# Connector.net
KiCad netlist of a schematic drawn in Altium Designer
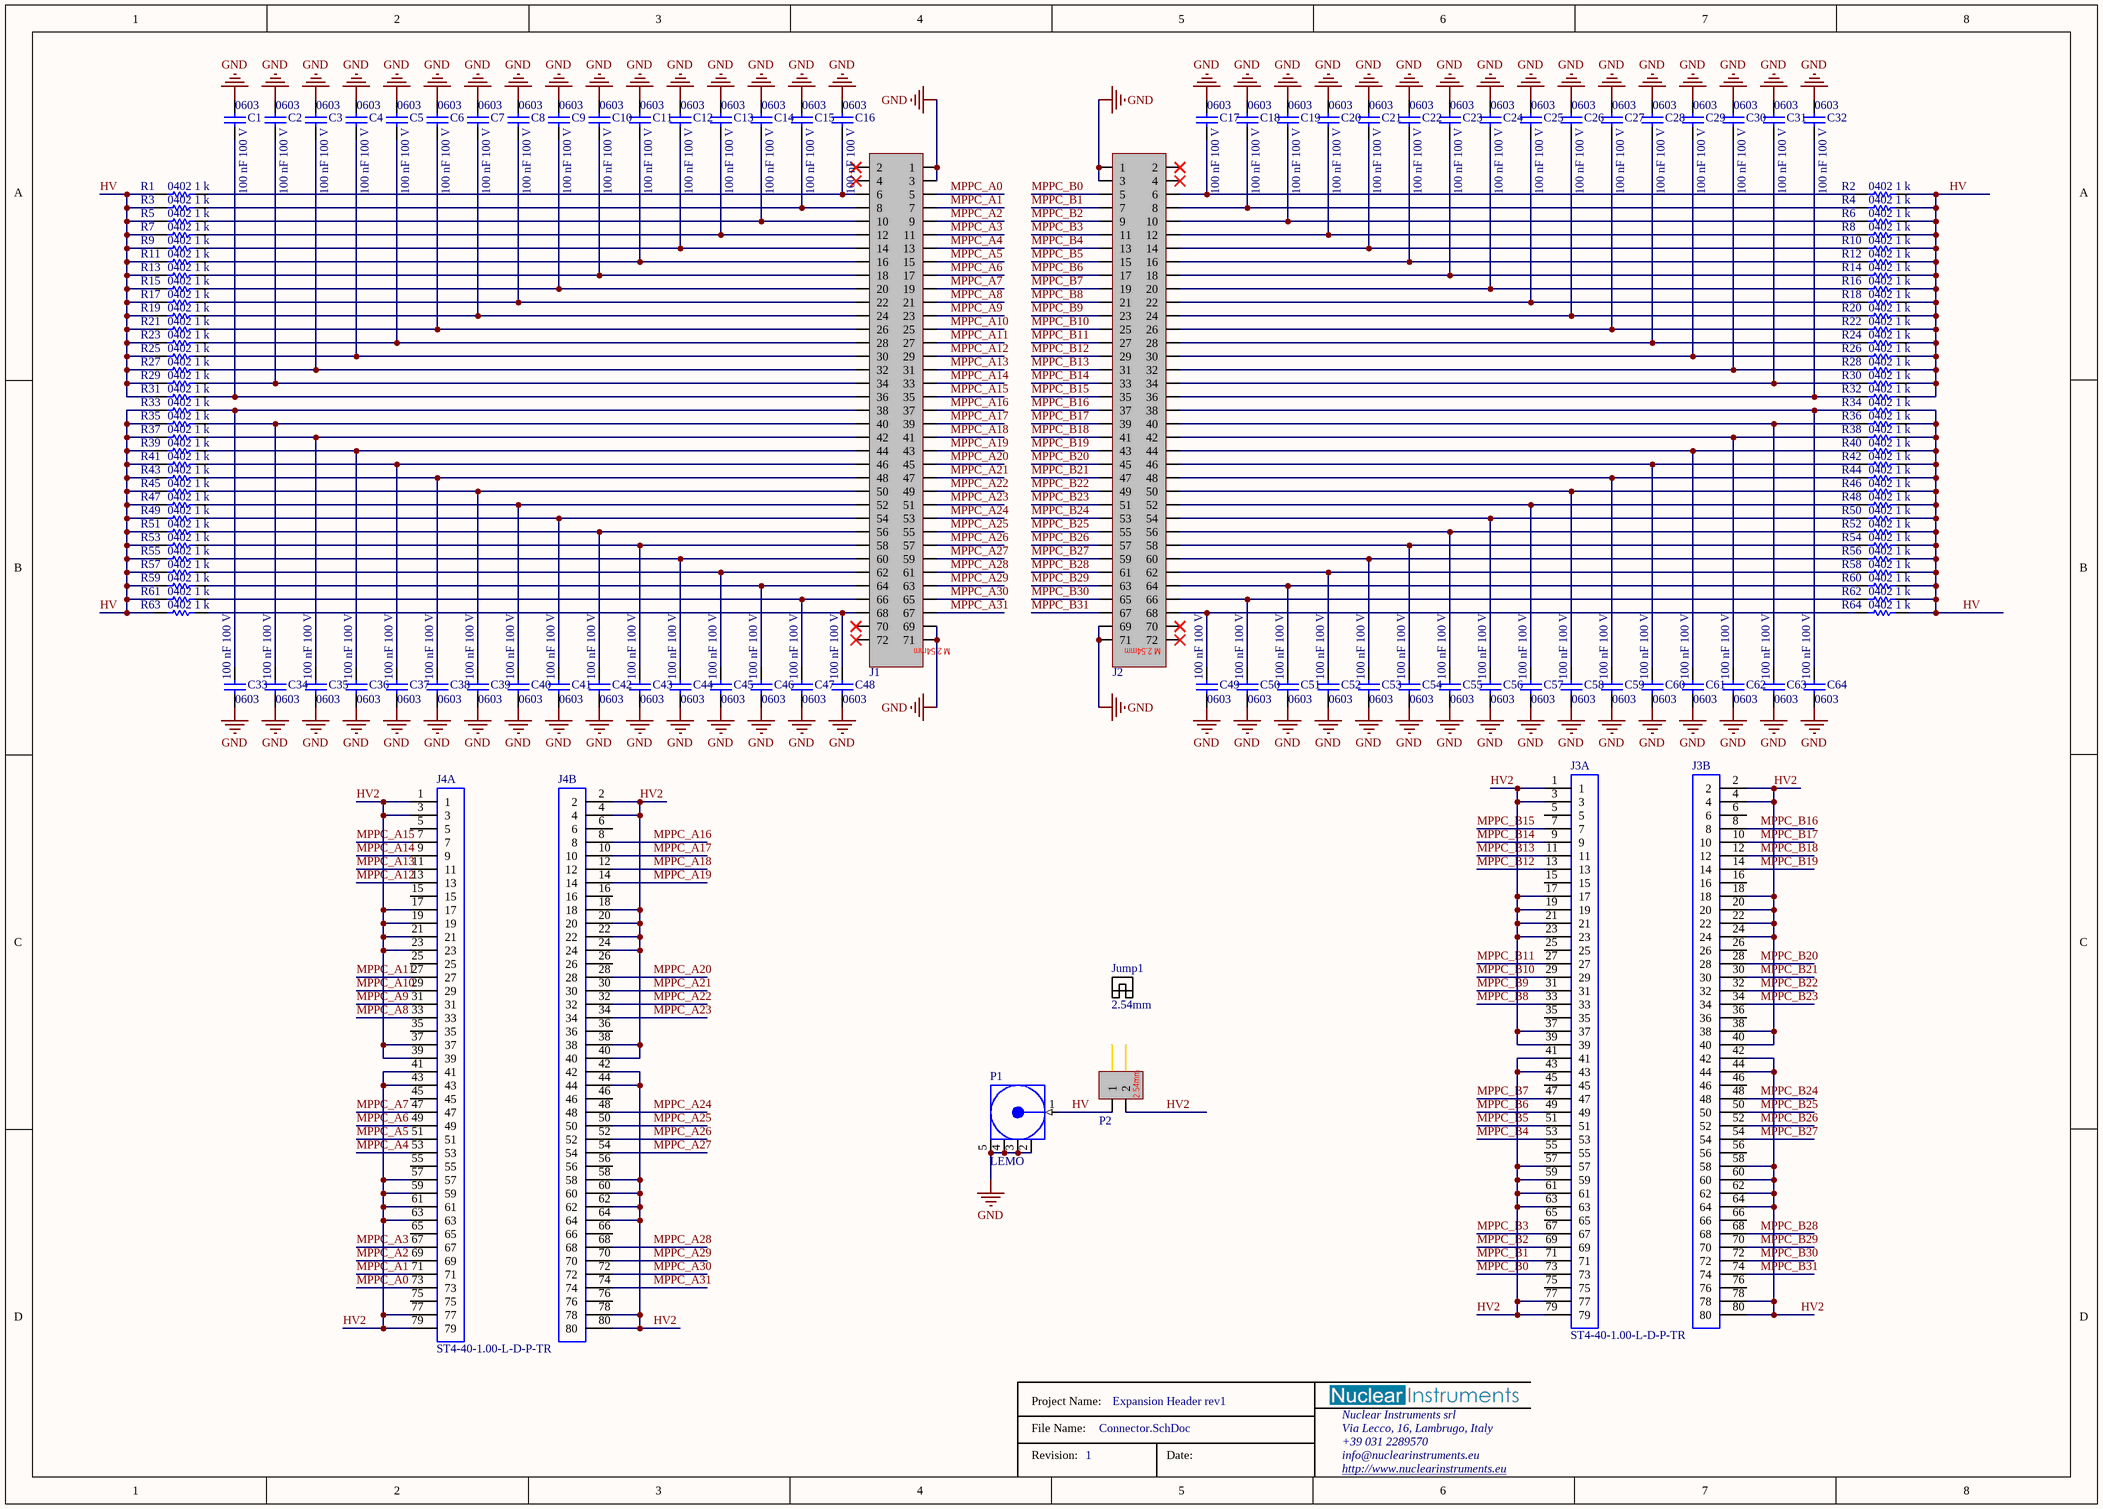
[diagram p0: Connector.SchDoc]

(export (version "E")
  (design (tool "Eeschema 10.0.6"))
  (components
    (comp (ref "C1")
      (value "0603")
      (footprint "CAPCERSMD0603")
      (fields (field (name "ALTIUM_VALUE") "100 nF 100 V"))
      (libsource (lib "0603_Cap_Cer__SARAversion-9") (part "CAPCER0603_X7R_100V_100n"))
    )
    (comp (ref "C2")
      (value "0603")
      (footprint "CAPCERSMD0603")
      (fields (field (name "ALTIUM_VALUE") "100 nF 100 V"))
      (libsource (lib "0603_Cap_Cer__SARAversion-9") (part "CAPCER0603_X7R_100V_100n"))
    )
    (comp (ref "C3")
      (value "0603")
      (footprint "CAPCERSMD0603")
      (fields (field (name "ALTIUM_VALUE") "100 nF 100 V"))
      (libsource (lib "0603_Cap_Cer__SARAversion-9") (part "CAPCER0603_X7R_100V_100n"))
    )
    (comp (ref "C4")
      (value "0603")
      (footprint "CAPCERSMD0603")
      (fields (field (name "ALTIUM_VALUE") "100 nF 100 V"))
      (libsource (lib "0603_Cap_Cer__SARAversion-9") (part "CAPCER0603_X7R_100V_100n"))
    )
    (comp (ref "C5")
      (value "0603")
      (footprint "CAPCERSMD0603")
      (fields (field (name "ALTIUM_VALUE") "100 nF 100 V"))
      (libsource (lib "0603_Cap_Cer__SARAversion-9") (part "CAPCER0603_X7R_100V_100n"))
    )
    (comp (ref "C6")
      (value "0603")
      (footprint "CAPCERSMD0603")
      (fields (field (name "ALTIUM_VALUE") "100 nF 100 V"))
      (libsource (lib "0603_Cap_Cer__SARAversion-9") (part "CAPCER0603_X7R_100V_100n"))
    )
    (comp (ref "C7")
      (value "0603")
      (footprint "CAPCERSMD0603")
      (fields (field (name "ALTIUM_VALUE") "100 nF 100 V"))
      (libsource (lib "0603_Cap_Cer__SARAversion-9") (part "CAPCER0603_X7R_100V_100n"))
    )
    (comp (ref "C8")
      (value "0603")
      (footprint "CAPCERSMD0603")
      (fields (field (name "ALTIUM_VALUE") "100 nF 100 V"))
      (libsource (lib "0603_Cap_Cer__SARAversion-9") (part "CAPCER0603_X7R_100V_100n"))
    )
    (comp (ref "C9")
      (value "0603")
      (footprint "CAPCERSMD0603")
      (fields (field (name "ALTIUM_VALUE") "100 nF 100 V"))
      (libsource (lib "0603_Cap_Cer__SARAversion-9") (part "CAPCER0603_X7R_100V_100n"))
    )
    (comp (ref "C10")
      (value "0603")
      (footprint "CAPCERSMD0603")
      (fields (field (name "ALTIUM_VALUE") "100 nF 100 V"))
      (libsource (lib "0603_Cap_Cer__SARAversion-9") (part "CAPCER0603_X7R_100V_100n"))
    )
    (comp (ref "C11")
      (value "0603")
      (footprint "CAPCERSMD0603")
      (fields (field (name "ALTIUM_VALUE") "100 nF 100 V"))
      (libsource (lib "0603_Cap_Cer__SARAversion-9") (part "CAPCER0603_X7R_100V_100n"))
    )
    (comp (ref "C12")
      (value "0603")
      (footprint "CAPCERSMD0603")
      (fields (field (name "ALTIUM_VALUE") "100 nF 100 V"))
      (libsource (lib "0603_Cap_Cer__SARAversion-9") (part "CAPCER0603_X7R_100V_100n"))
    )
    (comp (ref "C13")
      (value "0603")
      (footprint "CAPCERSMD0603")
      (fields (field (name "ALTIUM_VALUE") "100 nF 100 V"))
      (libsource (lib "0603_Cap_Cer__SARAversion-9") (part "CAPCER0603_X7R_100V_100n"))
    )
    (comp (ref "C14")
      (value "0603")
      (footprint "CAPCERSMD0603")
      (fields (field (name "ALTIUM_VALUE") "100 nF 100 V"))
      (libsource (lib "0603_Cap_Cer__SARAversion-9") (part "CAPCER0603_X7R_100V_100n"))
    )
    (comp (ref "C15")
      (value "0603")
      (footprint "CAPCERSMD0603")
      (fields (field (name "ALTIUM_VALUE") "100 nF 100 V"))
      (libsource (lib "0603_Cap_Cer__SARAversion-9") (part "CAPCER0603_X7R_100V_100n"))
    )
    (comp (ref "C16")
      (value "0603")
      (footprint "CAPCERSMD0603")
      (fields (field (name "ALTIUM_VALUE") "100 nF 100 V"))
      (libsource (lib "0603_Cap_Cer__SARAversion-9") (part "CAPCER0603_X7R_100V_100n"))
    )
    (comp (ref "C17")
      (value "0603")
      (footprint "CAPCERSMD0603")
      (fields (field (name "ALTIUM_VALUE") "100 nF 100 V"))
      (libsource (lib "0603_Cap_Cer__SARAversion-9") (part "CAPCER0603_X7R_100V_100n"))
    )
    (comp (ref "C18")
      (value "0603")
      (footprint "CAPCERSMD0603")
      (fields (field (name "ALTIUM_VALUE") "100 nF 100 V"))
      (libsource (lib "0603_Cap_Cer__SARAversion-9") (part "CAPCER0603_X7R_100V_100n"))
    )
    (comp (ref "C19")
      (value "0603")
      (footprint "CAPCERSMD0603")
      (fields (field (name "ALTIUM_VALUE") "100 nF 100 V"))
      (libsource (lib "0603_Cap_Cer__SARAversion-9") (part "CAPCER0603_X7R_100V_100n"))
    )
    (comp (ref "C20")
      (value "0603")
      (footprint "CAPCERSMD0603")
      (fields (field (name "ALTIUM_VALUE") "100 nF 100 V"))
      (libsource (lib "0603_Cap_Cer__SARAversion-9") (part "CAPCER0603_X7R_100V_100n"))
    )
    (comp (ref "C21")
      (value "0603")
      (footprint "CAPCERSMD0603")
      (fields (field (name "ALTIUM_VALUE") "100 nF 100 V"))
      (libsource (lib "0603_Cap_Cer__SARAversion-9") (part "CAPCER0603_X7R_100V_100n"))
    )
    (comp (ref "C22")
      (value "0603")
      (footprint "CAPCERSMD0603")
      (fields (field (name "ALTIUM_VALUE") "100 nF 100 V"))
      (libsource (lib "0603_Cap_Cer__SARAversion-9") (part "CAPCER0603_X7R_100V_100n"))
    )
    (comp (ref "C23")
      (value "0603")
      (footprint "CAPCERSMD0603")
      (fields (field (name "ALTIUM_VALUE") "100 nF 100 V"))
      (libsource (lib "0603_Cap_Cer__SARAversion-9") (part "CAPCER0603_X7R_100V_100n"))
    )
    (comp (ref "C24")
      (value "0603")
      (footprint "CAPCERSMD0603")
      (fields (field (name "ALTIUM_VALUE") "100 nF 100 V"))
      (libsource (lib "0603_Cap_Cer__SARAversion-9") (part "CAPCER0603_X7R_100V_100n"))
    )
    (comp (ref "C25")
      (value "0603")
      (footprint "CAPCERSMD0603")
      (fields (field (name "ALTIUM_VALUE") "100 nF 100 V"))
      (libsource (lib "0603_Cap_Cer__SARAversion-9") (part "CAPCER0603_X7R_100V_100n"))
    )
    (comp (ref "C26")
      (value "0603")
      (footprint "CAPCERSMD0603")
      (fields (field (name "ALTIUM_VALUE") "100 nF 100 V"))
      (libsource (lib "0603_Cap_Cer__SARAversion-9") (part "CAPCER0603_X7R_100V_100n"))
    )
    (comp (ref "C27")
      (value "0603")
      (footprint "CAPCERSMD0603")
      (fields (field (name "ALTIUM_VALUE") "100 nF 100 V"))
      (libsource (lib "0603_Cap_Cer__SARAversion-9") (part "CAPCER0603_X7R_100V_100n"))
    )
    (comp (ref "C28")
      (value "0603")
      (footprint "CAPCERSMD0603")
      (fields (field (name "ALTIUM_VALUE") "100 nF 100 V"))
      (libsource (lib "0603_Cap_Cer__SARAversion-9") (part "CAPCER0603_X7R_100V_100n"))
    )
    (comp (ref "C29")
      (value "0603")
      (footprint "CAPCERSMD0603")
      (fields (field (name "ALTIUM_VALUE") "100 nF 100 V"))
      (libsource (lib "0603_Cap_Cer__SARAversion-9") (part "CAPCER0603_X7R_100V_100n"))
    )
    (comp (ref "C30")
      (value "0603")
      (footprint "CAPCERSMD0603")
      (fields (field (name "ALTIUM_VALUE") "100 nF 100 V"))
      (libsource (lib "0603_Cap_Cer__SARAversion-9") (part "CAPCER0603_X7R_100V_100n"))
    )
    (comp (ref "C31")
      (value "0603")
      (footprint "CAPCERSMD0603")
      (fields (field (name "ALTIUM_VALUE") "100 nF 100 V"))
      (libsource (lib "0603_Cap_Cer__SARAversion-9") (part "CAPCER0603_X7R_100V_100n"))
    )
    (comp (ref "C32")
      (value "0603")
      (footprint "CAPCERSMD0603")
      (fields (field (name "ALTIUM_VALUE") "100 nF 100 V"))
      (libsource (lib "0603_Cap_Cer__SARAversion-9") (part "CAPCER0603_X7R_100V_100n"))
    )
    (comp (ref "C33")
      (value "0603")
      (footprint "CAPCERSMD0603")
      (fields (field (name "ALTIUM_VALUE") "100 nF 100 V"))
      (libsource (lib "0603_Cap_Cer__SARAversion-9") (part "CAPCER0603_X7R_100V_100n"))
    )
    (comp (ref "C34")
      (value "0603")
      (footprint "CAPCERSMD0603")
      (fields (field (name "ALTIUM_VALUE") "100 nF 100 V"))
      (libsource (lib "0603_Cap_Cer__SARAversion-9") (part "CAPCER0603_X7R_100V_100n"))
    )
    (comp (ref "C35")
      (value "0603")
      (footprint "CAPCERSMD0603")
      (fields (field (name "ALTIUM_VALUE") "100 nF 100 V"))
      (libsource (lib "0603_Cap_Cer__SARAversion-9") (part "CAPCER0603_X7R_100V_100n"))
    )
    (comp (ref "C36")
      (value "0603")
      (footprint "CAPCERSMD0603")
      (fields (field (name "ALTIUM_VALUE") "100 nF 100 V"))
      (libsource (lib "0603_Cap_Cer__SARAversion-9") (part "CAPCER0603_X7R_100V_100n"))
    )
    (comp (ref "C37")
      (value "0603")
      (footprint "CAPCERSMD0603")
      (fields (field (name "ALTIUM_VALUE") "100 nF 100 V"))
      (libsource (lib "0603_Cap_Cer__SARAversion-9") (part "CAPCER0603_X7R_100V_100n"))
    )
    (comp (ref "C38")
      (value "0603")
      (footprint "CAPCERSMD0603")
      (fields (field (name "ALTIUM_VALUE") "100 nF 100 V"))
      (libsource (lib "0603_Cap_Cer__SARAversion-9") (part "CAPCER0603_X7R_100V_100n"))
    )
    (comp (ref "C39")
      (value "0603")
      (footprint "CAPCERSMD0603")
      (fields (field (name "ALTIUM_VALUE") "100 nF 100 V"))
      (libsource (lib "0603_Cap_Cer__SARAversion-9") (part "CAPCER0603_X7R_100V_100n"))
    )
    (comp (ref "C40")
      (value "0603")
      (footprint "CAPCERSMD0603")
      (fields (field (name "ALTIUM_VALUE") "100 nF 100 V"))
      (libsource (lib "0603_Cap_Cer__SARAversion-9") (part "CAPCER0603_X7R_100V_100n"))
    )
    (comp (ref "C41")
      (value "0603")
      (footprint "CAPCERSMD0603")
      (fields (field (name "ALTIUM_VALUE") "100 nF 100 V"))
      (libsource (lib "0603_Cap_Cer__SARAversion-9") (part "CAPCER0603_X7R_100V_100n"))
    )
    (comp (ref "C42")
      (value "0603")
      (footprint "CAPCERSMD0603")
      (fields (field (name "ALTIUM_VALUE") "100 nF 100 V"))
      (libsource (lib "0603_Cap_Cer__SARAversion-9") (part "CAPCER0603_X7R_100V_100n"))
    )
    (comp (ref "C43")
      (value "0603")
      (footprint "CAPCERSMD0603")
      (fields (field (name "ALTIUM_VALUE") "100 nF 100 V"))
      (libsource (lib "0603_Cap_Cer__SARAversion-9") (part "CAPCER0603_X7R_100V_100n"))
    )
    (comp (ref "C44")
      (value "0603")
      (footprint "CAPCERSMD0603")
      (fields (field (name "ALTIUM_VALUE") "100 nF 100 V"))
      (libsource (lib "0603_Cap_Cer__SARAversion-9") (part "CAPCER0603_X7R_100V_100n"))
    )
    (comp (ref "C45")
      (value "0603")
      (footprint "CAPCERSMD0603")
      (fields (field (name "ALTIUM_VALUE") "100 nF 100 V"))
      (libsource (lib "0603_Cap_Cer__SARAversion-9") (part "CAPCER0603_X7R_100V_100n"))
    )
    (comp (ref "C46")
      (value "0603")
      (footprint "CAPCERSMD0603")
      (fields (field (name "ALTIUM_VALUE") "100 nF 100 V"))
      (libsource (lib "0603_Cap_Cer__SARAversion-9") (part "CAPCER0603_X7R_100V_100n"))
    )
    (comp (ref "C47")
      (value "0603")
      (footprint "CAPCERSMD0603")
      (fields (field (name "ALTIUM_VALUE") "100 nF 100 V"))
      (libsource (lib "0603_Cap_Cer__SARAversion-9") (part "CAPCER0603_X7R_100V_100n"))
    )
    (comp (ref "C48")
      (value "0603")
      (footprint "CAPCERSMD0603")
      (fields (field (name "ALTIUM_VALUE") "100 nF 100 V"))
      (libsource (lib "0603_Cap_Cer__SARAversion-9") (part "CAPCER0603_X7R_100V_100n"))
    )
    (comp (ref "C49")
      (value "0603")
      (footprint "CAPCERSMD0603")
      (fields (field (name "ALTIUM_VALUE") "100 nF 100 V"))
      (libsource (lib "0603_Cap_Cer__SARAversion-9") (part "CAPCER0603_X7R_100V_100n"))
    )
    (comp (ref "C50")
      (value "0603")
      (footprint "CAPCERSMD0603")
      (fields (field (name "ALTIUM_VALUE") "100 nF 100 V"))
      (libsource (lib "0603_Cap_Cer__SARAversion-9") (part "CAPCER0603_X7R_100V_100n"))
    )
    (comp (ref "C51")
      (value "0603")
      (footprint "CAPCERSMD0603")
      (fields (field (name "ALTIUM_VALUE") "100 nF 100 V"))
      (libsource (lib "0603_Cap_Cer__SARAversion-9") (part "CAPCER0603_X7R_100V_100n"))
    )
    (comp (ref "C52")
      (value "0603")
      (footprint "CAPCERSMD0603")
      (fields (field (name "ALTIUM_VALUE") "100 nF 100 V"))
      (libsource (lib "0603_Cap_Cer__SARAversion-9") (part "CAPCER0603_X7R_100V_100n"))
    )
    (comp (ref "C53")
      (value "0603")
      (footprint "CAPCERSMD0603")
      (fields (field (name "ALTIUM_VALUE") "100 nF 100 V"))
      (libsource (lib "0603_Cap_Cer__SARAversion-9") (part "CAPCER0603_X7R_100V_100n"))
    )
    (comp (ref "C54")
      (value "0603")
      (footprint "CAPCERSMD0603")
      (fields (field (name "ALTIUM_VALUE") "100 nF 100 V"))
      (libsource (lib "0603_Cap_Cer__SARAversion-9") (part "CAPCER0603_X7R_100V_100n"))
    )
    (comp (ref "C55")
      (value "0603")
      (footprint "CAPCERSMD0603")
      (fields (field (name "ALTIUM_VALUE") "100 nF 100 V"))
      (libsource (lib "0603_Cap_Cer__SARAversion-9") (part "CAPCER0603_X7R_100V_100n"))
    )
    (comp (ref "C56")
      (value "0603")
      (footprint "CAPCERSMD0603")
      (fields (field (name "ALTIUM_VALUE") "100 nF 100 V"))
      (libsource (lib "0603_Cap_Cer__SARAversion-9") (part "CAPCER0603_X7R_100V_100n"))
    )
    (comp (ref "C57")
      (value "0603")
      (footprint "CAPCERSMD0603")
      (fields (field (name "ALTIUM_VALUE") "100 nF 100 V"))
      (libsource (lib "0603_Cap_Cer__SARAversion-9") (part "CAPCER0603_X7R_100V_100n"))
    )
    (comp (ref "C58")
      (value "0603")
      (footprint "CAPCERSMD0603")
      (fields (field (name "ALTIUM_VALUE") "100 nF 100 V"))
      (libsource (lib "0603_Cap_Cer__SARAversion-9") (part "CAPCER0603_X7R_100V_100n"))
    )
    (comp (ref "C59")
      (value "0603")
      (footprint "CAPCERSMD0603")
      (fields (field (name "ALTIUM_VALUE") "100 nF 100 V"))
      (libsource (lib "0603_Cap_Cer__SARAversion-9") (part "CAPCER0603_X7R_100V_100n"))
    )
    (comp (ref "C60")
      (value "0603")
      (footprint "CAPCERSMD0603")
      (fields (field (name "ALTIUM_VALUE") "100 nF 100 V"))
      (libsource (lib "0603_Cap_Cer__SARAversion-9") (part "CAPCER0603_X7R_100V_100n"))
    )
    (comp (ref "C61")
      (value "0603")
      (footprint "CAPCERSMD0603")
      (fields (field (name "ALTIUM_VALUE") "100 nF 100 V"))
      (libsource (lib "0603_Cap_Cer__SARAversion-9") (part "CAPCER0603_X7R_100V_100n"))
    )
    (comp (ref "C62")
      (value "0603")
      (footprint "CAPCERSMD0603")
      (fields (field (name "ALTIUM_VALUE") "100 nF 100 V"))
      (libsource (lib "0603_Cap_Cer__SARAversion-9") (part "CAPCER0603_X7R_100V_100n"))
    )
    (comp (ref "C63")
      (value "0603")
      (footprint "CAPCERSMD0603")
      (fields (field (name "ALTIUM_VALUE") "100 nF 100 V"))
      (libsource (lib "0603_Cap_Cer__SARAversion-9") (part "CAPCER0603_X7R_100V_100n"))
    )
    (comp (ref "C64")
      (value "0603")
      (footprint "CAPCERSMD0603")
      (fields (field (name "ALTIUM_VALUE") "100 nF 100 V"))
      (libsource (lib "0603_Cap_Cer__SARAversion-9") (part "CAPCER0603_X7R_100V_100n"))
    )
    (comp (ref "J1")
      (value "Male 72 pin, dual row, 2.54 mm pitch")
      (footprint "Wurth_WR-PHD_male_2rows_vertical_2.54pitch_72ways")
      (description "WR-PHD 2.54 mm Dual Pin Header, 72p")
      (libsource (lib "Strip_Connectors__SARAversion-13") (part "Wurth_WR-PHD_male_2rows_vertical_2.54pitch_72ways"))
    )
    (comp (ref "J2")
      (value "Male 72 pin, dual row, 2.54 mm pitch")
      (footprint "Wurth_WR-PHD_male_2rows_vertical_2.54pitch_72ways")
      (description "WR-PHD 2.54 mm Dual Pin Header, 72p")
      (libsource (lib "") (part "Wurth_WR-PHD_male_2rows_vertical_2.54pitch_72ways_1"))
    )
    (comp (ref "J3")
      (value "ST4-40-1.00-L-D-P-TR")
      (footprint "Samtec_ST4-40-1.00-L-D-P-TR")
      (description "ULTRA FINE PITCH SOCKET")
      (libsource (lib "Board_Board_Connectors__SARAversion-51") (part "Samtec_ST4-40-1.00-L-D-P-TR"))
    )
    (comp (ref "J4")
      (value "ST4-40-1.00-L-D-P-TR")
      (footprint "Samtec_ST4-40-1.00-L-D-P-TR")
      (description "ULTRA FINE PITCH SOCKET")
      (libsource (lib "Board_Board_Connectors__SARAversion-51") (part "Samtec_ST4-40-1.00-L-D-P-TR"))
    )
    (comp (ref "Jump1") (value "2.54mm") (libsource (lib "Mechanical__SARAversion-68") (part "SNT-100-BK-G")))
    (comp (ref "P1")
      (value "LEMO")
      (footprint "LEMO_EPA.00.250.DTN_Vertical")
      (description "LEMO EPA 00 Vertical")
      (libsource (lib "Coaxial_Connectors__SARAversion-10") (part "LEMO_EPA.00.250.DTN_Vertical"))
    )
    (comp (ref "P2")
      (value "Wurth_WR-PHD_2way_2.54mm_male")
      (footprint "Wurth_WR-PHD_2way_2.54mm_male")
      (description "Male 2 way 2.54 mm")
      (libsource (lib "Strip_Connectors__SARAversion-13") (part "Wurth_WR-PHD_2way_2.54mm_male"))
    )
    (comp (ref "R1")
      (value "0402")
      (footprint "RESSMD0402")
      (fields (field (name "ALTIUM_VALUE") "1 k"))
      (libsource (lib "0402_Resistors__SARAversion-44") (part "RES0402-1k"))
    )
    (comp (ref "R2")
      (value "0402")
      (footprint "RESSMD0402")
      (fields (field (name "ALTIUM_VALUE") "1 k"))
      (libsource (lib "0402_Resistors__SARAversion-44") (part "RES0402-1k"))
    )
    (comp (ref "R3")
      (value "0402")
      (footprint "RESSMD0402")
      (fields (field (name "ALTIUM_VALUE") "1 k"))
      (libsource (lib "0402_Resistors__SARAversion-44") (part "RES0402-1k"))
    )
    (comp (ref "R4")
      (value "0402")
      (footprint "RESSMD0402")
      (fields (field (name "ALTIUM_VALUE") "1 k"))
      (libsource (lib "0402_Resistors__SARAversion-44") (part "RES0402-1k"))
    )
    (comp (ref "R5")
      (value "0402")
      (footprint "RESSMD0402")
      (fields (field (name "ALTIUM_VALUE") "1 k"))
      (libsource (lib "0402_Resistors__SARAversion-44") (part "RES0402-1k"))
    )
    (comp (ref "R6")
      (value "0402")
      (footprint "RESSMD0402")
      (fields (field (name "ALTIUM_VALUE") "1 k"))
      (libsource (lib "0402_Resistors__SARAversion-44") (part "RES0402-1k"))
    )
    (comp (ref "R7")
      (value "0402")
      (footprint "RESSMD0402")
      (fields (field (name "ALTIUM_VALUE") "1 k"))
      (libsource (lib "0402_Resistors__SARAversion-44") (part "RES0402-1k"))
    )
    (comp (ref "R8")
      (value "0402")
      (footprint "RESSMD0402")
      (fields (field (name "ALTIUM_VALUE") "1 k"))
      (libsource (lib "0402_Resistors__SARAversion-44") (part "RES0402-1k"))
    )
    (comp (ref "R9")
      (value "0402")
      (footprint "RESSMD0402")
      (fields (field (name "ALTIUM_VALUE") "1 k"))
      (libsource (lib "0402_Resistors__SARAversion-44") (part "RES0402-1k"))
    )
    (comp (ref "R10")
      (value "0402")
      (footprint "RESSMD0402")
      (fields (field (name "ALTIUM_VALUE") "1 k"))
      (libsource (lib "0402_Resistors__SARAversion-44") (part "RES0402-1k"))
    )
    (comp (ref "R11")
      (value "0402")
      (footprint "RESSMD0402")
      (fields (field (name "ALTIUM_VALUE") "1 k"))
      (libsource (lib "0402_Resistors__SARAversion-44") (part "RES0402-1k"))
    )
    (comp (ref "R12")
      (value "0402")
      (footprint "RESSMD0402")
      (fields (field (name "ALTIUM_VALUE") "1 k"))
      (libsource (lib "0402_Resistors__SARAversion-44") (part "RES0402-1k"))
    )
    (comp (ref "R13")
      (value "0402")
      (footprint "RESSMD0402")
      (fields (field (name "ALTIUM_VALUE") "1 k"))
      (libsource (lib "0402_Resistors__SARAversion-44") (part "RES0402-1k"))
    )
    (comp (ref "R14")
      (value "0402")
      (footprint "RESSMD0402")
      (fields (field (name "ALTIUM_VALUE") "1 k"))
      (libsource (lib "0402_Resistors__SARAversion-44") (part "RES0402-1k"))
    )
    (comp (ref "R15")
      (value "0402")
      (footprint "RESSMD0402")
      (fields (field (name "ALTIUM_VALUE") "1 k"))
      (libsource (lib "0402_Resistors__SARAversion-44") (part "RES0402-1k"))
    )
    (comp (ref "R16")
      (value "0402")
      (footprint "RESSMD0402")
      (fields (field (name "ALTIUM_VALUE") "1 k"))
      (libsource (lib "0402_Resistors__SARAversion-44") (part "RES0402-1k"))
    )
    (comp (ref "R17")
      (value "0402")
      (footprint "RESSMD0402")
      (fields (field (name "ALTIUM_VALUE") "1 k"))
      (libsource (lib "0402_Resistors__SARAversion-44") (part "RES0402-1k"))
    )
    (comp (ref "R18")
      (value "0402")
      (footprint "RESSMD0402")
      (fields (field (name "ALTIUM_VALUE") "1 k"))
      (libsource (lib "0402_Resistors__SARAversion-44") (part "RES0402-1k"))
    )
    (comp (ref "R19")
      (value "0402")
      (footprint "RESSMD0402")
      (fields (field (name "ALTIUM_VALUE") "1 k"))
      (libsource (lib "0402_Resistors__SARAversion-44") (part "RES0402-1k"))
    )
    (comp (ref "R20")
      (value "0402")
      (footprint "RESSMD0402")
      (fields (field (name "ALTIUM_VALUE") "1 k"))
      (libsource (lib "0402_Resistors__SARAversion-44") (part "RES0402-1k"))
    )
    (comp (ref "R21")
      (value "0402")
      (footprint "RESSMD0402")
      (fields (field (name "ALTIUM_VALUE") "1 k"))
      (libsource (lib "0402_Resistors__SARAversion-44") (part "RES0402-1k"))
    )
    (comp (ref "R22")
      (value "0402")
      (footprint "RESSMD0402")
      (fields (field (name "ALTIUM_VALUE") "1 k"))
      (libsource (lib "0402_Resistors__SARAversion-44") (part "RES0402-1k"))
    )
    (comp (ref "R23")
      (value "0402")
      (footprint "RESSMD0402")
      (fields (field (name "ALTIUM_VALUE") "1 k"))
      (libsource (lib "0402_Resistors__SARAversion-44") (part "RES0402-1k"))
    )
    (comp (ref "R24")
      (value "0402")
      (footprint "RESSMD0402")
      (fields (field (name "ALTIUM_VALUE") "1 k"))
      (libsource (lib "0402_Resistors__SARAversion-44") (part "RES0402-1k"))
    )
    (comp (ref "R25")
      (value "0402")
      (footprint "RESSMD0402")
      (fields (field (name "ALTIUM_VALUE") "1 k"))
      (libsource (lib "0402_Resistors__SARAversion-44") (part "RES0402-1k"))
    )
    (comp (ref "R26")
      (value "0402")
      (footprint "RESSMD0402")
      (fields (field (name "ALTIUM_VALUE") "1 k"))
      (libsource (lib "0402_Resistors__SARAversion-44") (part "RES0402-1k"))
    )
    (comp (ref "R27")
      (value "0402")
      (footprint "RESSMD0402")
      (fields (field (name "ALTIUM_VALUE") "1 k"))
      (libsource (lib "0402_Resistors__SARAversion-44") (part "RES0402-1k"))
    )
    (comp (ref "R28")
      (value "0402")
      (footprint "RESSMD0402")
      (fields (field (name "ALTIUM_VALUE") "1 k"))
      (libsource (lib "0402_Resistors__SARAversion-44") (part "RES0402-1k"))
    )
    (comp (ref "R29")
      (value "0402")
      (footprint "RESSMD0402")
      (fields (field (name "ALTIUM_VALUE") "1 k"))
      (libsource (lib "0402_Resistors__SARAversion-44") (part "RES0402-1k"))
    )
    (comp (ref "R30")
      (value "0402")
      (footprint "RESSMD0402")
      (fields (field (name "ALTIUM_VALUE") "1 k"))
      (libsource (lib "0402_Resistors__SARAversion-44") (part "RES0402-1k"))
    )
    (comp (ref "R31")
      (value "0402")
      (footprint "RESSMD0402")
      (fields (field (name "ALTIUM_VALUE") "1 k"))
      (libsource (lib "0402_Resistors__SARAversion-44") (part "RES0402-1k"))
    )
    (comp (ref "R32")
      (value "0402")
      (footprint "RESSMD0402")
      (fields (field (name "ALTIUM_VALUE") "1 k"))
      (libsource (lib "0402_Resistors__SARAversion-44") (part "RES0402-1k"))
    )
    (comp (ref "R33")
      (value "0402")
      (footprint "RESSMD0402")
      (fields (field (name "ALTIUM_VALUE") "1 k"))
      (libsource (lib "0402_Resistors__SARAversion-44") (part "RES0402-1k"))
    )
    (comp (ref "R34")
      (value "0402")
      (footprint "RESSMD0402")
      (fields (field (name "ALTIUM_VALUE") "1 k"))
      (libsource (lib "0402_Resistors__SARAversion-44") (part "RES0402-1k"))
    )
    (comp (ref "R35")
      (value "0402")
      (footprint "RESSMD0402")
      (fields (field (name "ALTIUM_VALUE") "1 k"))
      (libsource (lib "0402_Resistors__SARAversion-44") (part "RES0402-1k"))
    )
    (comp (ref "R36")
      (value "0402")
      (footprint "RESSMD0402")
      (fields (field (name "ALTIUM_VALUE") "1 k"))
      (libsource (lib "0402_Resistors__SARAversion-44") (part "RES0402-1k"))
    )
    (comp (ref "R37")
      (value "0402")
      (footprint "RESSMD0402")
      (fields (field (name "ALTIUM_VALUE") "1 k"))
      (libsource (lib "0402_Resistors__SARAversion-44") (part "RES0402-1k"))
    )
    (comp (ref "R38")
      (value "0402")
      (footprint "RESSMD0402")
      (fields (field (name "ALTIUM_VALUE") "1 k"))
      (libsource (lib "0402_Resistors__SARAversion-44") (part "RES0402-1k"))
    )
    (comp (ref "R39")
      (value "0402")
      (footprint "RESSMD0402")
      (fields (field (name "ALTIUM_VALUE") "1 k"))
      (libsource (lib "0402_Resistors__SARAversion-44") (part "RES0402-1k"))
    )
    (comp (ref "R40")
      (value "0402")
      (footprint "RESSMD0402")
      (fields (field (name "ALTIUM_VALUE") "1 k"))
      (libsource (lib "0402_Resistors__SARAversion-44") (part "RES0402-1k"))
    )
    (comp (ref "R41")
      (value "0402")
      (footprint "RESSMD0402")
      (fields (field (name "ALTIUM_VALUE") "1 k"))
      (libsource (lib "0402_Resistors__SARAversion-44") (part "RES0402-1k"))
    )
    (comp (ref "R42")
      (value "0402")
      (footprint "RESSMD0402")
      (fields (field (name "ALTIUM_VALUE") "1 k"))
      (libsource (lib "0402_Resistors__SARAversion-44") (part "RES0402-1k"))
    )
    (comp (ref "R43")
      (value "0402")
      (footprint "RESSMD0402")
      (fields (field (name "ALTIUM_VALUE") "1 k"))
      (libsource (lib "0402_Resistors__SARAversion-44") (part "RES0402-1k"))
    )
    (comp (ref "R44")
      (value "0402")
      (footprint "RESSMD0402")
      (fields (field (name "ALTIUM_VALUE") "1 k"))
      (libsource (lib "0402_Resistors__SARAversion-44") (part "RES0402-1k"))
    )
    (comp (ref "R45")
      (value "0402")
      (footprint "RESSMD0402")
      (fields (field (name "ALTIUM_VALUE") "1 k"))
      (libsource (lib "0402_Resistors__SARAversion-44") (part "RES0402-1k"))
    )
    (comp (ref "R46")
      (value "0402")
      (footprint "RESSMD0402")
      (fields (field (name "ALTIUM_VALUE") "1 k"))
      (libsource (lib "0402_Resistors__SARAversion-44") (part "RES0402-1k"))
    )
    (comp (ref "R47")
      (value "0402")
      (footprint "RESSMD0402")
      (fields (field (name "ALTIUM_VALUE") "1 k"))
      (libsource (lib "0402_Resistors__SARAversion-44") (part "RES0402-1k"))
    )
    (comp (ref "R48")
      (value "0402")
      (footprint "RESSMD0402")
      (fields (field (name "ALTIUM_VALUE") "1 k"))
      (libsource (lib "0402_Resistors__SARAversion-44") (part "RES0402-1k"))
    )
    (comp (ref "R49")
      (value "0402")
      (footprint "RESSMD0402")
      (fields (field (name "ALTIUM_VALUE") "1 k"))
      (libsource (lib "0402_Resistors__SARAversion-44") (part "RES0402-1k"))
    )
    (comp (ref "R50")
      (value "0402")
      (footprint "RESSMD0402")
      (fields (field (name "ALTIUM_VALUE") "1 k"))
      (libsource (lib "0402_Resistors__SARAversion-44") (part "RES0402-1k"))
    )
    (comp (ref "R51")
      (value "0402")
      (footprint "RESSMD0402")
      (fields (field (name "ALTIUM_VALUE") "1 k"))
      (libsource (lib "0402_Resistors__SARAversion-44") (part "RES0402-1k"))
    )
    (comp (ref "R52")
      (value "0402")
      (footprint "RESSMD0402")
      (fields (field (name "ALTIUM_VALUE") "1 k"))
      (libsource (lib "0402_Resistors__SARAversion-44") (part "RES0402-1k"))
    )
    (comp (ref "R53")
      (value "0402")
      (footprint "RESSMD0402")
      (fields (field (name "ALTIUM_VALUE") "1 k"))
      (libsource (lib "0402_Resistors__SARAversion-44") (part "RES0402-1k"))
    )
    (comp (ref "R54")
      (value "0402")
      (footprint "RESSMD0402")
      (fields (field (name "ALTIUM_VALUE") "1 k"))
      (libsource (lib "0402_Resistors__SARAversion-44") (part "RES0402-1k"))
    )
    (comp (ref "R55")
      (value "0402")
      (footprint "RESSMD0402")
      (fields (field (name "ALTIUM_VALUE") "1 k"))
      (libsource (lib "0402_Resistors__SARAversion-44") (part "RES0402-1k"))
    )
    (comp (ref "R56")
      (value "0402")
      (footprint "RESSMD0402")
      (fields (field (name "ALTIUM_VALUE") "1 k"))
      (libsource (lib "0402_Resistors__SARAversion-44") (part "RES0402-1k"))
    )
    (comp (ref "R57")
      (value "0402")
      (footprint "RESSMD0402")
      (fields (field (name "ALTIUM_VALUE") "1 k"))
      (libsource (lib "0402_Resistors__SARAversion-44") (part "RES0402-1k"))
    )
    (comp (ref "R58")
      (value "0402")
      (footprint "RESSMD0402")
      (fields (field (name "ALTIUM_VALUE") "1 k"))
      (libsource (lib "0402_Resistors__SARAversion-44") (part "RES0402-1k"))
    )
    (comp (ref "R59")
      (value "0402")
      (footprint "RESSMD0402")
      (fields (field (name "ALTIUM_VALUE") "1 k"))
      (libsource (lib "0402_Resistors__SARAversion-44") (part "RES0402-1k"))
    )
    (comp (ref "R60")
      (value "0402")
      (footprint "RESSMD0402")
      (fields (field (name "ALTIUM_VALUE") "1 k"))
      (libsource (lib "0402_Resistors__SARAversion-44") (part "RES0402-1k"))
    )
    (comp (ref "R61")
      (value "0402")
      (footprint "RESSMD0402")
      (fields (field (name "ALTIUM_VALUE") "1 k"))
      (libsource (lib "0402_Resistors__SARAversion-44") (part "RES0402-1k"))
    )
    (comp (ref "R62")
      (value "0402")
      (footprint "RESSMD0402")
      (fields (field (name "ALTIUM_VALUE") "1 k"))
      (libsource (lib "0402_Resistors__SARAversion-44") (part "RES0402-1k"))
    )
    (comp (ref "R63")
      (value "0402")
      (footprint "RESSMD0402")
      (fields (field (name "ALTIUM_VALUE") "1 k"))
      (libsource (lib "0402_Resistors__SARAversion-44") (part "RES0402-1k"))
    )
    (comp (ref "R64")
      (value "0402")
      (footprint "RESSMD0402")
      (fields (field (name "ALTIUM_VALUE") "1 k"))
      (libsource (lib "0402_Resistors__SARAversion-44") (part "RES0402-1k"))
    )
  )
  (nets
    (net (code "1") (name "/HV") (class "Default")
      (node (ref "P1") (pin "1") (pinfunction "Signal_1") (pintype "input"))
      (node (ref "P2") (pin "1") (pinfunction "1_1") (pintype "passive"))
      (node (ref "R1") (pin "1") (pinfunction "1_1") (pintype "passive"))
      (node (ref "R10") (pin "2") (pinfunction "2_2") (pintype "passive"))
      (node (ref "R11") (pin "1") (pinfunction "1_1") (pintype "passive"))
      (node (ref "R12") (pin "2") (pinfunction "2_2") (pintype "passive"))
      (node (ref "R13") (pin "1") (pinfunction "1_1") (pintype "passive"))
      (node (ref "R14") (pin "2") (pinfunction "2_2") (pintype "passive"))
      (node (ref "R15") (pin "1") (pinfunction "1_1") (pintype "passive"))
      (node (ref "R16") (pin "2") (pinfunction "2_2") (pintype "passive"))
      (node (ref "R17") (pin "1") (pinfunction "1_1") (pintype "passive"))
      (node (ref "R18") (pin "2") (pinfunction "2_2") (pintype "passive"))
      (node (ref "R19") (pin "1") (pinfunction "1_1") (pintype "passive"))
      (node (ref "R2") (pin "2") (pinfunction "2_2") (pintype "passive"))
      (node (ref "R20") (pin "2") (pinfunction "2_2") (pintype "passive"))
      (node (ref "R21") (pin "1") (pinfunction "1_1") (pintype "passive"))
      (node (ref "R22") (pin "2") (pinfunction "2_2") (pintype "passive"))
      (node (ref "R23") (pin "1") (pinfunction "1_1") (pintype "passive"))
      (node (ref "R24") (pin "2") (pinfunction "2_2") (pintype "passive"))
      (node (ref "R25") (pin "1") (pinfunction "1_1") (pintype "passive"))
      (node (ref "R26") (pin "2") (pinfunction "2_2") (pintype "passive"))
      (node (ref "R27") (pin "1") (pinfunction "1_1") (pintype "passive"))
      (node (ref "R28") (pin "2") (pinfunction "2_2") (pintype "passive"))
      (node (ref "R29") (pin "1") (pinfunction "1_1") (pintype "passive"))
      (node (ref "R3") (pin "1") (pinfunction "1_1") (pintype "passive"))
      (node (ref "R30") (pin "2") (pinfunction "2_2") (pintype "passive"))
      (node (ref "R31") (pin "1") (pinfunction "1_1") (pintype "passive"))
      (node (ref "R32") (pin "2") (pinfunction "2_2") (pintype "passive"))
      (node (ref "R33") (pin "1") (pinfunction "1_1") (pintype "passive"))
      (node (ref "R34") (pin "2") (pinfunction "2_2") (pintype "passive"))
      (node (ref "R35") (pin "1") (pinfunction "1_1") (pintype "passive"))
      (node (ref "R36") (pin "2") (pinfunction "2_2") (pintype "passive"))
      (node (ref "R37") (pin "1") (pinfunction "1_1") (pintype "passive"))
      (node (ref "R38") (pin "2") (pinfunction "2_2") (pintype "passive"))
      (node (ref "R39") (pin "1") (pinfunction "1_1") (pintype "passive"))
      (node (ref "R4") (pin "2") (pinfunction "2_2") (pintype "passive"))
      (node (ref "R40") (pin "2") (pinfunction "2_2") (pintype "passive"))
      (node (ref "R41") (pin "1") (pinfunction "1_1") (pintype "passive"))
      (node (ref "R42") (pin "2") (pinfunction "2_2") (pintype "passive"))
      (node (ref "R43") (pin "1") (pinfunction "1_1") (pintype "passive"))
      (node (ref "R44") (pin "2") (pinfunction "2_2") (pintype "passive"))
      (node (ref "R45") (pin "1") (pinfunction "1_1") (pintype "passive"))
      (node (ref "R46") (pin "2") (pinfunction "2_2") (pintype "passive"))
      (node (ref "R47") (pin "1") (pinfunction "1_1") (pintype "passive"))
      (node (ref "R48") (pin "2") (pinfunction "2_2") (pintype "passive"))
      (node (ref "R49") (pin "1") (pinfunction "1_1") (pintype "passive"))
      (node (ref "R5") (pin "1") (pinfunction "1_1") (pintype "passive"))
      (node (ref "R50") (pin "2") (pinfunction "2_2") (pintype "passive"))
      (node (ref "R51") (pin "1") (pinfunction "1_1") (pintype "passive"))
      (node (ref "R52") (pin "2") (pinfunction "2_2") (pintype "passive"))
      (node (ref "R53") (pin "1") (pinfunction "1_1") (pintype "passive"))
      (node (ref "R54") (pin "2") (pinfunction "2_2") (pintype "passive"))
      (node (ref "R55") (pin "1") (pinfunction "1_1") (pintype "passive"))
      (node (ref "R56") (pin "2") (pinfunction "2_2") (pintype "passive"))
      (node (ref "R57") (pin "1") (pinfunction "1_1") (pintype "passive"))
      (node (ref "R58") (pin "2") (pinfunction "2_2") (pintype "passive"))
      (node (ref "R59") (pin "1") (pinfunction "1_1") (pintype "passive"))
      (node (ref "R6") (pin "2") (pinfunction "2_2") (pintype "passive"))
      (node (ref "R60") (pin "2") (pinfunction "2_2") (pintype "passive"))
      (node (ref "R61") (pin "1") (pinfunction "1_1") (pintype "passive"))
      (node (ref "R62") (pin "2") (pinfunction "2_2") (pintype "passive"))
      (node (ref "R63") (pin "1") (pinfunction "1_1") (pintype "passive"))
      (node (ref "R64") (pin "2") (pinfunction "2_2") (pintype "passive"))
      (node (ref "R7") (pin "1") (pinfunction "1_1") (pintype "passive"))
      (node (ref "R8") (pin "2") (pinfunction "2_2") (pintype "passive"))
      (node (ref "R9") (pin "1") (pinfunction "1_1") (pintype "passive"))
    )
    (net (code "2") (name "/HV2") (class "Default")
      (node (ref "J3") (pin "1") (pinfunction "1_1") (pintype "passive"))
      (node (ref "J3") (pin "17") (pinfunction "17_17") (pintype "passive"))
      (node (ref "J3") (pin "18") (pinfunction "18_18") (pintype "passive"))
      (node (ref "J3") (pin "19") (pinfunction "19_19") (pintype "passive"))
      (node (ref "J3") (pin "2") (pinfunction "2_2") (pintype "passive"))
      (node (ref "J3") (pin "20") (pinfunction "20_20") (pintype "passive"))
      (node (ref "J3") (pin "21") (pinfunction "21_21") (pintype "passive"))
      (node (ref "J3") (pin "22") (pinfunction "22_22") (pintype "passive"))
      (node (ref "J3") (pin "23") (pinfunction "23_23") (pintype "passive"))
      (node (ref "J3") (pin "24") (pinfunction "24_24") (pintype "passive"))
      (node (ref "J3") (pin "3") (pinfunction "3_3") (pintype "passive"))
      (node (ref "J3") (pin "37") (pinfunction "37_37") (pintype "passive"))
      (node (ref "J3") (pin "38") (pinfunction "38_38") (pintype "passive"))
      (node (ref "J3") (pin "39") (pinfunction "39_39") (pintype "passive"))
      (node (ref "J3") (pin "4") (pinfunction "4_4") (pintype "passive"))
      (node (ref "J3") (pin "40") (pinfunction "40_40") (pintype "passive"))
      (node (ref "J3") (pin "41") (pinfunction "41_41") (pintype "passive"))
      (node (ref "J3") (pin "42") (pinfunction "42_42") (pintype "passive"))
      (node (ref "J3") (pin "43") (pinfunction "43_43") (pintype "passive"))
      (node (ref "J3") (pin "44") (pinfunction "44_44") (pintype "passive"))
      (node (ref "J3") (pin "57") (pinfunction "57_57") (pintype "passive"))
      (node (ref "J3") (pin "58") (pinfunction "58_58") (pintype "passive"))
      (node (ref "J3") (pin "59") (pinfunction "59_59") (pintype "passive"))
      (node (ref "J3") (pin "60") (pinfunction "60_60") (pintype "passive"))
      (node (ref "J3") (pin "61") (pinfunction "61_61") (pintype "passive"))
      (node (ref "J3") (pin "62") (pinfunction "62_62") (pintype "passive"))
      (node (ref "J3") (pin "63") (pinfunction "63_63") (pintype "passive"))
      (node (ref "J3") (pin "64") (pinfunction "64_64") (pintype "passive"))
      (node (ref "J3") (pin "77") (pinfunction "77_77") (pintype "passive"))
      (node (ref "J3") (pin "78") (pinfunction "78_78") (pintype "passive"))
      (node (ref "J3") (pin "79") (pinfunction "79_79") (pintype "passive"))
      (node (ref "J3") (pin "80") (pinfunction "80_80") (pintype "passive"))
      (node (ref "J4") (pin "1") (pinfunction "1_1") (pintype "passive"))
      (node (ref "J4") (pin "17") (pinfunction "17_17") (pintype "passive"))
      (node (ref "J4") (pin "18") (pinfunction "18_18") (pintype "passive"))
      (node (ref "J4") (pin "19") (pinfunction "19_19") (pintype "passive"))
      (node (ref "J4") (pin "2") (pinfunction "2_2") (pintype "passive"))
      (node (ref "J4") (pin "20") (pinfunction "20_20") (pintype "passive"))
      (node (ref "J4") (pin "21") (pinfunction "21_21") (pintype "passive"))
      (node (ref "J4") (pin "22") (pinfunction "22_22") (pintype "passive"))
      (node (ref "J4") (pin "23") (pinfunction "23_23") (pintype "passive"))
      (node (ref "J4") (pin "24") (pinfunction "24_24") (pintype "passive"))
      (node (ref "J4") (pin "3") (pinfunction "3_3") (pintype "passive"))
      (node (ref "J4") (pin "37") (pinfunction "37_37") (pintype "passive"))
      (node (ref "J4") (pin "38") (pinfunction "38_38") (pintype "passive"))
      (node (ref "J4") (pin "39") (pinfunction "39_39") (pintype "passive"))
      (node (ref "J4") (pin "4") (pinfunction "4_4") (pintype "passive"))
      (node (ref "J4") (pin "40") (pinfunction "40_40") (pintype "passive"))
      (node (ref "J4") (pin "41") (pinfunction "41_41") (pintype "passive"))
      (node (ref "J4") (pin "42") (pinfunction "42_42") (pintype "passive"))
      (node (ref "J4") (pin "43") (pinfunction "43_43") (pintype "passive"))
      (node (ref "J4") (pin "44") (pinfunction "44_44") (pintype "passive"))
      (node (ref "J4") (pin "57") (pinfunction "57_57") (pintype "passive"))
      (node (ref "J4") (pin "58") (pinfunction "58_58") (pintype "passive"))
      (node (ref "J4") (pin "59") (pinfunction "59_59") (pintype "passive"))
      (node (ref "J4") (pin "60") (pinfunction "60_60") (pintype "passive"))
      (node (ref "J4") (pin "61") (pinfunction "61_61") (pintype "passive"))
      (node (ref "J4") (pin "62") (pinfunction "62_62") (pintype "passive"))
      (node (ref "J4") (pin "63") (pinfunction "63_63") (pintype "passive"))
      (node (ref "J4") (pin "64") (pinfunction "64_64") (pintype "passive"))
      (node (ref "J4") (pin "77") (pinfunction "77_77") (pintype "passive"))
      (node (ref "J4") (pin "78") (pinfunction "78_78") (pintype "passive"))
      (node (ref "J4") (pin "79") (pinfunction "79_79") (pintype "passive"))
      (node (ref "J4") (pin "80") (pinfunction "80_80") (pintype "passive"))
      (node (ref "P2") (pin "2") (pinfunction "2_2") (pintype "passive"))
    )
    (net (code "3") (name "/MPPC_A0") (class "Default")
      (node (ref "J1") (pin "5") (pinfunction "5_5") (pintype "passive"))
      (node (ref "J4") (pin "73") (pinfunction "73_73") (pintype "passive"))
    )
    (net (code "4") (name "/MPPC_A1") (class "Default")
      (node (ref "J1") (pin "7") (pinfunction "7_7") (pintype "passive"))
      (node (ref "J4") (pin "71") (pinfunction "71_71") (pintype "passive"))
    )
    (net (code "5") (name "/MPPC_A2") (class "Default")
      (node (ref "J1") (pin "9") (pinfunction "9_9") (pintype "passive"))
      (node (ref "J4") (pin "69") (pinfunction "69_69") (pintype "passive"))
    )
    (net (code "6") (name "/MPPC_A3") (class "Default")
      (node (ref "J1") (pin "11") (pinfunction "11_11") (pintype "passive"))
      (node (ref "J4") (pin "67") (pinfunction "67_67") (pintype "passive"))
    )
    (net (code "7") (name "/MPPC_A4") (class "Default")
      (node (ref "J1") (pin "13") (pinfunction "13_13") (pintype "passive"))
      (node (ref "J4") (pin "53") (pinfunction "53_53") (pintype "passive"))
    )
    (net (code "8") (name "/MPPC_A5") (class "Default")
      (node (ref "J1") (pin "15") (pinfunction "15_15") (pintype "passive"))
      (node (ref "J4") (pin "51") (pinfunction "51_51") (pintype "passive"))
    )
    (net (code "9") (name "/MPPC_A6") (class "Default")
      (node (ref "J1") (pin "17") (pinfunction "17_17") (pintype "passive"))
      (node (ref "J4") (pin "49") (pinfunction "49_49") (pintype "passive"))
    )
    (net (code "10") (name "/MPPC_A7") (class "Default")
      (node (ref "J1") (pin "19") (pinfunction "19_19") (pintype "passive"))
      (node (ref "J4") (pin "47") (pinfunction "47_47") (pintype "passive"))
    )
    (net (code "11") (name "/MPPC_A8") (class "Default")
      (node (ref "J1") (pin "21") (pinfunction "21_21") (pintype "passive"))
      (node (ref "J4") (pin "33") (pinfunction "33_33") (pintype "passive"))
    )
    (net (code "12") (name "/MPPC_A9") (class "Default")
      (node (ref "J1") (pin "23") (pinfunction "23_23") (pintype "passive"))
      (node (ref "J4") (pin "31") (pinfunction "31_31") (pintype "passive"))
    )
    (net (code "13") (name "/MPPC_A10") (class "Default")
      (node (ref "J1") (pin "25") (pinfunction "25_25") (pintype "passive"))
      (node (ref "J4") (pin "29") (pinfunction "29_29") (pintype "passive"))
    )
    (net (code "14") (name "/MPPC_A11") (class "Default")
      (node (ref "J1") (pin "27") (pinfunction "27_27") (pintype "passive"))
      (node (ref "J4") (pin "27") (pinfunction "27_27") (pintype "passive"))
    )
    (net (code "15") (name "/MPPC_A12") (class "Default")
      (node (ref "J1") (pin "29") (pinfunction "29_29") (pintype "passive"))
      (node (ref "J4") (pin "13") (pinfunction "13_13") (pintype "passive"))
    )
    (net (code "16") (name "/MPPC_A13") (class "Default")
      (node (ref "J1") (pin "31") (pinfunction "31_31") (pintype "passive"))
      (node (ref "J4") (pin "11") (pinfunction "11_11") (pintype "passive"))
    )
    (net (code "17") (name "/MPPC_A14") (class "Default")
      (node (ref "J1") (pin "33") (pinfunction "33_33") (pintype "passive"))
      (node (ref "J4") (pin "9") (pinfunction "9_9") (pintype "passive"))
    )
    (net (code "18") (name "/MPPC_A15") (class "Default")
      (node (ref "J1") (pin "35") (pinfunction "35_35") (pintype "passive"))
      (node (ref "J4") (pin "7") (pinfunction "7_7") (pintype "passive"))
    )
    (net (code "19") (name "/MPPC_A16") (class "Default")
      (node (ref "J1") (pin "37") (pinfunction "37_37") (pintype "passive"))
      (node (ref "J4") (pin "8") (pinfunction "8_8") (pintype "passive"))
    )
    (net (code "20") (name "/MPPC_A17") (class "Default")
      (node (ref "J1") (pin "39") (pinfunction "39_39") (pintype "passive"))
      (node (ref "J4") (pin "10") (pinfunction "10_10") (pintype "passive"))
    )
    (net (code "21") (name "/MPPC_A18") (class "Default")
      (node (ref "J1") (pin "41") (pinfunction "41_41") (pintype "passive"))
      (node (ref "J4") (pin "12") (pinfunction "12_12") (pintype "passive"))
    )
    (net (code "22") (name "/MPPC_A19") (class "Default")
      (node (ref "J1") (pin "43") (pinfunction "43_43") (pintype "passive"))
      (node (ref "J4") (pin "14") (pinfunction "14_14") (pintype "passive"))
    )
    (net (code "23") (name "/MPPC_A20") (class "Default")
      (node (ref "J1") (pin "45") (pinfunction "45_45") (pintype "passive"))
      (node (ref "J4") (pin "28") (pinfunction "28_28") (pintype "passive"))
    )
    (net (code "24") (name "/MPPC_A21") (class "Default")
      (node (ref "J1") (pin "47") (pinfunction "47_47") (pintype "passive"))
      (node (ref "J4") (pin "30") (pinfunction "30_30") (pintype "passive"))
    )
    (net (code "25") (name "/MPPC_A22") (class "Default")
      (node (ref "J1") (pin "49") (pinfunction "49_49") (pintype "passive"))
      (node (ref "J4") (pin "32") (pinfunction "32_32") (pintype "passive"))
    )
    (net (code "26") (name "/MPPC_A23") (class "Default")
      (node (ref "J1") (pin "51") (pinfunction "51_51") (pintype "passive"))
      (node (ref "J4") (pin "34") (pinfunction "34_34") (pintype "passive"))
    )
    (net (code "27") (name "/MPPC_A24") (class "Default")
      (node (ref "J1") (pin "53") (pinfunction "53_53") (pintype "passive"))
      (node (ref "J4") (pin "48") (pinfunction "48_48") (pintype "passive"))
    )
    (net (code "28") (name "/MPPC_A25") (class "Default")
      (node (ref "J1") (pin "55") (pinfunction "55_55") (pintype "passive"))
      (node (ref "J4") (pin "50") (pinfunction "50_50") (pintype "passive"))
    )
    (net (code "29") (name "/MPPC_A26") (class "Default")
      (node (ref "J1") (pin "57") (pinfunction "57_57") (pintype "passive"))
      (node (ref "J4") (pin "52") (pinfunction "52_52") (pintype "passive"))
    )
    (net (code "30") (name "/MPPC_A27") (class "Default")
      (node (ref "J1") (pin "59") (pinfunction "59_59") (pintype "passive"))
      (node (ref "J4") (pin "54") (pinfunction "54_54") (pintype "passive"))
    )
    (net (code "31") (name "/MPPC_A28") (class "Default")
      (node (ref "J1") (pin "61") (pinfunction "61_61") (pintype "passive"))
      (node (ref "J4") (pin "68") (pinfunction "68_68") (pintype "passive"))
    )
    (net (code "32") (name "/MPPC_A29") (class "Default")
      (node (ref "J1") (pin "63") (pinfunction "63_63") (pintype "passive"))
      (node (ref "J4") (pin "70") (pinfunction "70_70") (pintype "passive"))
    )
    (net (code "33") (name "/MPPC_A30") (class "Default")
      (node (ref "J1") (pin "65") (pinfunction "65_65") (pintype "passive"))
      (node (ref "J4") (pin "72") (pinfunction "72_72") (pintype "passive"))
    )
    (net (code "34") (name "/MPPC_A31") (class "Default")
      (node (ref "J1") (pin "67") (pinfunction "67_67") (pintype "passive"))
      (node (ref "J4") (pin "74") (pinfunction "74_74") (pintype "passive"))
    )
    (net (code "35") (name "/MPPC_B0") (class "Default")
      (node (ref "J2") (pin "5") (pinfunction "5_5") (pintype "passive"))
      (node (ref "J3") (pin "73") (pinfunction "73_73") (pintype "passive"))
    )
    (net (code "36") (name "/MPPC_B1") (class "Default")
      (node (ref "J2") (pin "7") (pinfunction "7_7") (pintype "passive"))
      (node (ref "J3") (pin "71") (pinfunction "71_71") (pintype "passive"))
    )
    (net (code "37") (name "/MPPC_B2") (class "Default")
      (node (ref "J2") (pin "9") (pinfunction "9_9") (pintype "passive"))
      (node (ref "J3") (pin "69") (pinfunction "69_69") (pintype "passive"))
    )
    (net (code "38") (name "/MPPC_B3") (class "Default")
      (node (ref "J2") (pin "11") (pinfunction "11_11") (pintype "passive"))
      (node (ref "J3") (pin "67") (pinfunction "67_67") (pintype "passive"))
    )
    (net (code "39") (name "/MPPC_B4") (class "Default")
      (node (ref "J2") (pin "13") (pinfunction "13_13") (pintype "passive"))
      (node (ref "J3") (pin "53") (pinfunction "53_53") (pintype "passive"))
    )
    (net (code "40") (name "/MPPC_B5") (class "Default")
      (node (ref "J2") (pin "15") (pinfunction "15_15") (pintype "passive"))
      (node (ref "J3") (pin "51") (pinfunction "51_51") (pintype "passive"))
    )
    (net (code "41") (name "/MPPC_B6") (class "Default")
      (node (ref "J2") (pin "17") (pinfunction "17_17") (pintype "passive"))
      (node (ref "J3") (pin "49") (pinfunction "49_49") (pintype "passive"))
    )
    (net (code "42") (name "/MPPC_B7") (class "Default")
      (node (ref "J2") (pin "19") (pinfunction "19_19") (pintype "passive"))
      (node (ref "J3") (pin "47") (pinfunction "47_47") (pintype "passive"))
    )
    (net (code "43") (name "/MPPC_B8") (class "Default")
      (node (ref "J2") (pin "21") (pinfunction "21_21") (pintype "passive"))
      (node (ref "J3") (pin "33") (pinfunction "33_33") (pintype "passive"))
    )
    (net (code "44") (name "/MPPC_B9") (class "Default")
      (node (ref "J2") (pin "23") (pinfunction "23_23") (pintype "passive"))
      (node (ref "J3") (pin "31") (pinfunction "31_31") (pintype "passive"))
    )
    (net (code "45") (name "/MPPC_B10") (class "Default")
      (node (ref "J2") (pin "25") (pinfunction "25_25") (pintype "passive"))
      (node (ref "J3") (pin "29") (pinfunction "29_29") (pintype "passive"))
    )
    (net (code "46") (name "/MPPC_B11") (class "Default")
      (node (ref "J2") (pin "27") (pinfunction "27_27") (pintype "passive"))
      (node (ref "J3") (pin "27") (pinfunction "27_27") (pintype "passive"))
    )
    (net (code "47") (name "/MPPC_B12") (class "Default")
      (node (ref "J2") (pin "29") (pinfunction "29_29") (pintype "passive"))
      (node (ref "J3") (pin "13") (pinfunction "13_13") (pintype "passive"))
    )
    (net (code "48") (name "/MPPC_B13") (class "Default")
      (node (ref "J2") (pin "31") (pinfunction "31_31") (pintype "passive"))
      (node (ref "J3") (pin "11") (pinfunction "11_11") (pintype "passive"))
    )
    (net (code "49") (name "/MPPC_B14") (class "Default")
      (node (ref "J2") (pin "33") (pinfunction "33_33") (pintype "passive"))
      (node (ref "J3") (pin "9") (pinfunction "9_9") (pintype "passive"))
    )
    (net (code "50") (name "/MPPC_B15") (class "Default")
      (node (ref "J2") (pin "35") (pinfunction "35_35") (pintype "passive"))
      (node (ref "J3") (pin "7") (pinfunction "7_7") (pintype "passive"))
    )
    (net (code "51") (name "/MPPC_B16") (class "Default")
      (node (ref "J2") (pin "37") (pinfunction "37_37") (pintype "passive"))
      (node (ref "J3") (pin "8") (pinfunction "8_8") (pintype "passive"))
    )
    (net (code "52") (name "/MPPC_B17") (class "Default")
      (node (ref "J2") (pin "39") (pinfunction "39_39") (pintype "passive"))
      (node (ref "J3") (pin "10") (pinfunction "10_10") (pintype "passive"))
    )
    (net (code "53") (name "/MPPC_B18") (class "Default")
      (node (ref "J2") (pin "41") (pinfunction "41_41") (pintype "passive"))
      (node (ref "J3") (pin "12") (pinfunction "12_12") (pintype "passive"))
    )
    (net (code "54") (name "/MPPC_B19") (class "Default")
      (node (ref "J2") (pin "43") (pinfunction "43_43") (pintype "passive"))
      (node (ref "J3") (pin "14") (pinfunction "14_14") (pintype "passive"))
    )
    (net (code "55") (name "/MPPC_B20") (class "Default")
      (node (ref "J2") (pin "45") (pinfunction "45_45") (pintype "passive"))
      (node (ref "J3") (pin "28") (pinfunction "28_28") (pintype "passive"))
    )
    (net (code "56") (name "/MPPC_B21") (class "Default")
      (node (ref "J2") (pin "47") (pinfunction "47_47") (pintype "passive"))
      (node (ref "J3") (pin "30") (pinfunction "30_30") (pintype "passive"))
    )
    (net (code "57") (name "/MPPC_B22") (class "Default")
      (node (ref "J2") (pin "49") (pinfunction "49_49") (pintype "passive"))
      (node (ref "J3") (pin "32") (pinfunction "32_32") (pintype "passive"))
    )
    (net (code "58") (name "/MPPC_B23") (class "Default")
      (node (ref "J2") (pin "51") (pinfunction "51_51") (pintype "passive"))
      (node (ref "J3") (pin "34") (pinfunction "34_34") (pintype "passive"))
    )
    (net (code "59") (name "/MPPC_B24") (class "Default")
      (node (ref "J2") (pin "53") (pinfunction "53_53") (pintype "passive"))
      (node (ref "J3") (pin "48") (pinfunction "48_48") (pintype "passive"))
    )
    (net (code "60") (name "/MPPC_B25") (class "Default")
      (node (ref "J2") (pin "55") (pinfunction "55_55") (pintype "passive"))
      (node (ref "J3") (pin "50") (pinfunction "50_50") (pintype "passive"))
    )
    (net (code "61") (name "/MPPC_B26") (class "Default")
      (node (ref "J2") (pin "57") (pinfunction "57_57") (pintype "passive"))
      (node (ref "J3") (pin "52") (pinfunction "52_52") (pintype "passive"))
    )
    (net (code "62") (name "/MPPC_B27") (class "Default")
      (node (ref "J2") (pin "59") (pinfunction "59_59") (pintype "passive"))
      (node (ref "J3") (pin "54") (pinfunction "54_54") (pintype "passive"))
    )
    (net (code "63") (name "/MPPC_B28") (class "Default")
      (node (ref "J2") (pin "61") (pinfunction "61_61") (pintype "passive"))
      (node (ref "J3") (pin "68") (pinfunction "68_68") (pintype "passive"))
    )
    (net (code "64") (name "/MPPC_B29") (class "Default")
      (node (ref "J2") (pin "63") (pinfunction "63_63") (pintype "passive"))
      (node (ref "J3") (pin "70") (pinfunction "70_70") (pintype "passive"))
    )
    (net (code "65") (name "/MPPC_B30") (class "Default")
      (node (ref "J2") (pin "65") (pinfunction "65_65") (pintype "passive"))
      (node (ref "J3") (pin "72") (pinfunction "72_72") (pintype "passive"))
    )
    (net (code "66") (name "/MPPC_B31") (class "Default")
      (node (ref "J2") (pin "67") (pinfunction "67_67") (pintype "passive"))
      (node (ref "J3") (pin "74") (pinfunction "74_74") (pintype "passive"))
    )
    (net (code "67") (name "GND") (class "Default")
      (node (ref "C1") (pin "2") (pinfunction "2_2") (pintype "passive"))
      (node (ref "C10") (pin "2") (pinfunction "2_2") (pintype "passive"))
      (node (ref "C11") (pin "2") (pinfunction "2_2") (pintype "passive"))
      (node (ref "C12") (pin "2") (pinfunction "2_2") (pintype "passive"))
      (node (ref "C13") (pin "2") (pinfunction "2_2") (pintype "passive"))
      (node (ref "C14") (pin "2") (pinfunction "2_2") (pintype "passive"))
      (node (ref "C15") (pin "2") (pinfunction "2_2") (pintype "passive"))
      (node (ref "C16") (pin "2") (pinfunction "2_2") (pintype "passive"))
      (node (ref "C17") (pin "2") (pinfunction "2_2") (pintype "passive"))
      (node (ref "C18") (pin "2") (pinfunction "2_2") (pintype "passive"))
      (node (ref "C19") (pin "2") (pinfunction "2_2") (pintype "passive"))
      (node (ref "C2") (pin "2") (pinfunction "2_2") (pintype "passive"))
      (node (ref "C20") (pin "2") (pinfunction "2_2") (pintype "passive"))
      (node (ref "C21") (pin "2") (pinfunction "2_2") (pintype "passive"))
      (node (ref "C22") (pin "2") (pinfunction "2_2") (pintype "passive"))
      (node (ref "C23") (pin "2") (pinfunction "2_2") (pintype "passive"))
      (node (ref "C24") (pin "2") (pinfunction "2_2") (pintype "passive"))
      (node (ref "C25") (pin "2") (pinfunction "2_2") (pintype "passive"))
      (node (ref "C26") (pin "2") (pinfunction "2_2") (pintype "passive"))
      (node (ref "C27") (pin "2") (pinfunction "2_2") (pintype "passive"))
      (node (ref "C28") (pin "2") (pinfunction "2_2") (pintype "passive"))
      (node (ref "C29") (pin "2") (pinfunction "2_2") (pintype "passive"))
      (node (ref "C3") (pin "2") (pinfunction "2_2") (pintype "passive"))
      (node (ref "C30") (pin "2") (pinfunction "2_2") (pintype "passive"))
      (node (ref "C31") (pin "2") (pinfunction "2_2") (pintype "passive"))
      (node (ref "C32") (pin "2") (pinfunction "2_2") (pintype "passive"))
      (node (ref "C33") (pin "2") (pinfunction "2_2") (pintype "passive"))
      (node (ref "C34") (pin "2") (pinfunction "2_2") (pintype "passive"))
      (node (ref "C35") (pin "2") (pinfunction "2_2") (pintype "passive"))
      (node (ref "C36") (pin "2") (pinfunction "2_2") (pintype "passive"))
      (node (ref "C37") (pin "2") (pinfunction "2_2") (pintype "passive"))
      (node (ref "C38") (pin "2") (pinfunction "2_2") (pintype "passive"))
      (node (ref "C39") (pin "2") (pinfunction "2_2") (pintype "passive"))
      (node (ref "C4") (pin "2") (pinfunction "2_2") (pintype "passive"))
      (node (ref "C40") (pin "2") (pinfunction "2_2") (pintype "passive"))
      (node (ref "C41") (pin "2") (pinfunction "2_2") (pintype "passive"))
      (node (ref "C42") (pin "2") (pinfunction "2_2") (pintype "passive"))
      (node (ref "C43") (pin "2") (pinfunction "2_2") (pintype "passive"))
      (node (ref "C44") (pin "2") (pinfunction "2_2") (pintype "passive"))
      (node (ref "C45") (pin "2") (pinfunction "2_2") (pintype "passive"))
      (node (ref "C46") (pin "2") (pinfunction "2_2") (pintype "passive"))
      (node (ref "C47") (pin "2") (pinfunction "2_2") (pintype "passive"))
      (node (ref "C48") (pin "2") (pinfunction "2_2") (pintype "passive"))
      (node (ref "C49") (pin "2") (pinfunction "2_2") (pintype "passive"))
      (node (ref "C5") (pin "2") (pinfunction "2_2") (pintype "passive"))
      (node (ref "C50") (pin "2") (pinfunction "2_2") (pintype "passive"))
      (node (ref "C51") (pin "2") (pinfunction "2_2") (pintype "passive"))
      (node (ref "C52") (pin "2") (pinfunction "2_2") (pintype "passive"))
      (node (ref "C53") (pin "2") (pinfunction "2_2") (pintype "passive"))
      (node (ref "C54") (pin "2") (pinfunction "2_2") (pintype "passive"))
      (node (ref "C55") (pin "2") (pinfunction "2_2") (pintype "passive"))
      (node (ref "C56") (pin "2") (pinfunction "2_2") (pintype "passive"))
      (node (ref "C57") (pin "2") (pinfunction "2_2") (pintype "passive"))
      (node (ref "C58") (pin "2") (pinfunction "2_2") (pintype "passive"))
      (node (ref "C59") (pin "2") (pinfunction "2_2") (pintype "passive"))
      (node (ref "C6") (pin "2") (pinfunction "2_2") (pintype "passive"))
      (node (ref "C60") (pin "2") (pinfunction "2_2") (pintype "passive"))
      (node (ref "C61") (pin "2") (pinfunction "2_2") (pintype "passive"))
      (node (ref "C62") (pin "2") (pinfunction "2_2") (pintype "passive"))
      (node (ref "C63") (pin "2") (pinfunction "2_2") (pintype "passive"))
      (node (ref "C64") (pin "2") (pinfunction "2_2") (pintype "passive"))
      (node (ref "C7") (pin "2") (pinfunction "2_2") (pintype "passive"))
      (node (ref "C8") (pin "2") (pinfunction "2_2") (pintype "passive"))
      (node (ref "C9") (pin "2") (pinfunction "2_2") (pintype "passive"))
      (node (ref "J1") (pin "1") (pinfunction "1_1") (pintype "passive"))
      (node (ref "J1") (pin "3") (pinfunction "3_3") (pintype "passive"))
      (node (ref "J1") (pin "69") (pinfunction "69_69") (pintype "passive"))
      (node (ref "J1") (pin "71") (pinfunction "71_71") (pintype "passive"))
      (node (ref "J2") (pin "1") (pinfunction "1_1") (pintype "passive"))
      (node (ref "J2") (pin "3") (pinfunction "3_3") (pintype "passive"))
      (node (ref "J2") (pin "69") (pinfunction "69_69") (pintype "passive"))
      (node (ref "J2") (pin "71") (pinfunction "71_71") (pintype "passive"))
      (node (ref "P1") (pin "2") (pinfunction "GND_2") (pintype "power_in"))
      (node (ref "P1") (pin "3") (pinfunction "GND_3") (pintype "power_in"))
      (node (ref "P1") (pin "4") (pinfunction "GND_4") (pintype "power_in"))
      (node (ref "P1") (pin "5") (pinfunction "GND_5") (pintype "power_in"))
    )
    (net (code "68") (name "Net-(C1-Pad1)") (class "Default")
      (node (ref "C1") (pin "1") (pinfunction "1_1") (pintype "passive"))
      (node (ref "J1") (pin "36") (pinfunction "36_36") (pintype "passive"))
      (node (ref "R31") (pin "2") (pinfunction "2_2") (pintype "passive"))
    )
    (net (code "69") (name "Net-(C2-Pad1)") (class "Default")
      (node (ref "C2") (pin "1") (pinfunction "1_1") (pintype "passive"))
      (node (ref "J1") (pin "34") (pinfunction "34_34") (pintype "passive"))
      (node (ref "R29") (pin "2") (pinfunction "2_2") (pintype "passive"))
    )
    (net (code "70") (name "Net-(C3-Pad1)") (class "Default")
      (node (ref "C3") (pin "1") (pinfunction "1_1") (pintype "passive"))
      (node (ref "J1") (pin "32") (pinfunction "32_32") (pintype "passive"))
      (node (ref "R27") (pin "2") (pinfunction "2_2") (pintype "passive"))
    )
    (net (code "71") (name "Net-(C4-Pad1)") (class "Default")
      (node (ref "C4") (pin "1") (pinfunction "1_1") (pintype "passive"))
      (node (ref "J1") (pin "30") (pinfunction "30_30") (pintype "passive"))
      (node (ref "R25") (pin "2") (pinfunction "2_2") (pintype "passive"))
    )
    (net (code "72") (name "Net-(C5-Pad1)") (class "Default")
      (node (ref "C5") (pin "1") (pinfunction "1_1") (pintype "passive"))
      (node (ref "J1") (pin "28") (pinfunction "28_28") (pintype "passive"))
      (node (ref "R23") (pin "2") (pinfunction "2_2") (pintype "passive"))
    )
    (net (code "73") (name "Net-(C6-Pad1)") (class "Default")
      (node (ref "C6") (pin "1") (pinfunction "1_1") (pintype "passive"))
      (node (ref "J1") (pin "26") (pinfunction "26_26") (pintype "passive"))
      (node (ref "R21") (pin "2") (pinfunction "2_2") (pintype "passive"))
    )
    (net (code "74") (name "Net-(C7-Pad1)") (class "Default")
      (node (ref "C7") (pin "1") (pinfunction "1_1") (pintype "passive"))
      (node (ref "J1") (pin "24") (pinfunction "24_24") (pintype "passive"))
      (node (ref "R19") (pin "2") (pinfunction "2_2") (pintype "passive"))
    )
    (net (code "75") (name "Net-(C8-Pad1)") (class "Default")
      (node (ref "C8") (pin "1") (pinfunction "1_1") (pintype "passive"))
      (node (ref "J1") (pin "22") (pinfunction "22_22") (pintype "passive"))
      (node (ref "R17") (pin "2") (pinfunction "2_2") (pintype "passive"))
    )
    (net (code "76") (name "Net-(C9-Pad1)") (class "Default")
      (node (ref "C9") (pin "1") (pinfunction "1_1") (pintype "passive"))
      (node (ref "J1") (pin "20") (pinfunction "20_20") (pintype "passive"))
      (node (ref "R15") (pin "2") (pinfunction "2_2") (pintype "passive"))
    )
    (net (code "77") (name "Net-(C10-Pad1)") (class "Default")
      (node (ref "C10") (pin "1") (pinfunction "1_1") (pintype "passive"))
      (node (ref "J1") (pin "18") (pinfunction "18_18") (pintype "passive"))
      (node (ref "R13") (pin "2") (pinfunction "2_2") (pintype "passive"))
    )
    (net (code "78") (name "Net-(C11-Pad1)") (class "Default")
      (node (ref "C11") (pin "1") (pinfunction "1_1") (pintype "passive"))
      (node (ref "J1") (pin "16") (pinfunction "16_16") (pintype "passive"))
      (node (ref "R11") (pin "2") (pinfunction "2_2") (pintype "passive"))
    )
    (net (code "79") (name "Net-(C12-Pad1)") (class "Default")
      (node (ref "C12") (pin "1") (pinfunction "1_1") (pintype "passive"))
      (node (ref "J1") (pin "14") (pinfunction "14_14") (pintype "passive"))
      (node (ref "R9") (pin "2") (pinfunction "2_2") (pintype "passive"))
    )
    (net (code "80") (name "Net-(C13-Pad1)") (class "Default")
      (node (ref "C13") (pin "1") (pinfunction "1_1") (pintype "passive"))
      (node (ref "J1") (pin "12") (pinfunction "12_12") (pintype "passive"))
      (node (ref "R7") (pin "2") (pinfunction "2_2") (pintype "passive"))
    )
    (net (code "81") (name "Net-(C14-Pad1)") (class "Default")
      (node (ref "C14") (pin "1") (pinfunction "1_1") (pintype "passive"))
      (node (ref "J1") (pin "10") (pinfunction "10_10") (pintype "passive"))
      (node (ref "R5") (pin "2") (pinfunction "2_2") (pintype "passive"))
    )
    (net (code "82") (name "Net-(C15-Pad1)") (class "Default")
      (node (ref "C15") (pin "1") (pinfunction "1_1") (pintype "passive"))
      (node (ref "J1") (pin "8") (pinfunction "8_8") (pintype "passive"))
      (node (ref "R3") (pin "2") (pinfunction "2_2") (pintype "passive"))
    )
    (net (code "83") (name "Net-(C16-Pad1)") (class "Default")
      (node (ref "C16") (pin "1") (pinfunction "1_1") (pintype "passive"))
      (node (ref "J1") (pin "6") (pinfunction "6_6") (pintype "passive"))
      (node (ref "R1") (pin "2") (pinfunction "2_2") (pintype "passive"))
    )
    (net (code "84") (name "Net-(C17-Pad1)") (class "Default")
      (node (ref "C17") (pin "1") (pinfunction "1_1") (pintype "passive"))
      (node (ref "J2") (pin "6") (pinfunction "6_6") (pintype "passive"))
      (node (ref "R2") (pin "1") (pinfunction "1_1") (pintype "passive"))
    )
    (net (code "85") (name "Net-(C18-Pad1)") (class "Default")
      (node (ref "C18") (pin "1") (pinfunction "1_1") (pintype "passive"))
      (node (ref "J2") (pin "8") (pinfunction "8_8") (pintype "passive"))
      (node (ref "R4") (pin "1") (pinfunction "1_1") (pintype "passive"))
    )
    (net (code "86") (name "Net-(C19-Pad1)") (class "Default")
      (node (ref "C19") (pin "1") (pinfunction "1_1") (pintype "passive"))
      (node (ref "J2") (pin "10") (pinfunction "10_10") (pintype "passive"))
      (node (ref "R6") (pin "1") (pinfunction "1_1") (pintype "passive"))
    )
    (net (code "87") (name "Net-(C20-Pad1)") (class "Default")
      (node (ref "C20") (pin "1") (pinfunction "1_1") (pintype "passive"))
      (node (ref "J2") (pin "12") (pinfunction "12_12") (pintype "passive"))
      (node (ref "R8") (pin "1") (pinfunction "1_1") (pintype "passive"))
    )
    (net (code "88") (name "Net-(C21-Pad1)") (class "Default")
      (node (ref "C21") (pin "1") (pinfunction "1_1") (pintype "passive"))
      (node (ref "J2") (pin "14") (pinfunction "14_14") (pintype "passive"))
      (node (ref "R10") (pin "1") (pinfunction "1_1") (pintype "passive"))
    )
    (net (code "89") (name "Net-(C22-Pad1)") (class "Default")
      (node (ref "C22") (pin "1") (pinfunction "1_1") (pintype "passive"))
      (node (ref "J2") (pin "16") (pinfunction "16_16") (pintype "passive"))
      (node (ref "R12") (pin "1") (pinfunction "1_1") (pintype "passive"))
    )
    (net (code "90") (name "Net-(C23-Pad1)") (class "Default")
      (node (ref "C23") (pin "1") (pinfunction "1_1") (pintype "passive"))
      (node (ref "J2") (pin "18") (pinfunction "18_18") (pintype "passive"))
      (node (ref "R14") (pin "1") (pinfunction "1_1") (pintype "passive"))
    )
    (net (code "91") (name "Net-(C24-Pad1)") (class "Default")
      (node (ref "C24") (pin "1") (pinfunction "1_1") (pintype "passive"))
      (node (ref "J2") (pin "20") (pinfunction "20_20") (pintype "passive"))
      (node (ref "R16") (pin "1") (pinfunction "1_1") (pintype "passive"))
    )
    (net (code "92") (name "Net-(C25-Pad1)") (class "Default")
      (node (ref "C25") (pin "1") (pinfunction "1_1") (pintype "passive"))
      (node (ref "J2") (pin "22") (pinfunction "22_22") (pintype "passive"))
      (node (ref "R18") (pin "1") (pinfunction "1_1") (pintype "passive"))
    )
    (net (code "93") (name "Net-(C26-Pad1)") (class "Default")
      (node (ref "C26") (pin "1") (pinfunction "1_1") (pintype "passive"))
      (node (ref "J2") (pin "24") (pinfunction "24_24") (pintype "passive"))
      (node (ref "R20") (pin "1") (pinfunction "1_1") (pintype "passive"))
    )
    (net (code "94") (name "Net-(C27-Pad1)") (class "Default")
      (node (ref "C27") (pin "1") (pinfunction "1_1") (pintype "passive"))
      (node (ref "J2") (pin "26") (pinfunction "26_26") (pintype "passive"))
      (node (ref "R22") (pin "1") (pinfunction "1_1") (pintype "passive"))
    )
    (net (code "95") (name "Net-(C28-Pad1)") (class "Default")
      (node (ref "C28") (pin "1") (pinfunction "1_1") (pintype "passive"))
      (node (ref "J2") (pin "28") (pinfunction "28_28") (pintype "passive"))
      (node (ref "R24") (pin "1") (pinfunction "1_1") (pintype "passive"))
    )
    (net (code "96") (name "Net-(C29-Pad1)") (class "Default")
      (node (ref "C29") (pin "1") (pinfunction "1_1") (pintype "passive"))
      (node (ref "J2") (pin "30") (pinfunction "30_30") (pintype "passive"))
      (node (ref "R26") (pin "1") (pinfunction "1_1") (pintype "passive"))
    )
    (net (code "97") (name "Net-(C30-Pad1)") (class "Default")
      (node (ref "C30") (pin "1") (pinfunction "1_1") (pintype "passive"))
      (node (ref "J2") (pin "32") (pinfunction "32_32") (pintype "passive"))
      (node (ref "R28") (pin "1") (pinfunction "1_1") (pintype "passive"))
    )
    (net (code "98") (name "Net-(C31-Pad1)") (class "Default")
      (node (ref "C31") (pin "1") (pinfunction "1_1") (pintype "passive"))
      (node (ref "J2") (pin "34") (pinfunction "34_34") (pintype "passive"))
      (node (ref "R30") (pin "1") (pinfunction "1_1") (pintype "passive"))
    )
    (net (code "99") (name "Net-(C32-Pad1)") (class "Default")
      (node (ref "C32") (pin "1") (pinfunction "1_1") (pintype "passive"))
      (node (ref "J2") (pin "36") (pinfunction "36_36") (pintype "passive"))
      (node (ref "R32") (pin "1") (pinfunction "1_1") (pintype "passive"))
    )
    (net (code "100") (name "Net-(C33-Pad1)") (class "Default")
      (node (ref "C33") (pin "1") (pinfunction "1_1") (pintype "passive"))
      (node (ref "J1") (pin "38") (pinfunction "38_38") (pintype "passive"))
      (node (ref "R33") (pin "2") (pinfunction "2_2") (pintype "passive"))
    )
    (net (code "101") (name "Net-(C34-Pad1)") (class "Default")
      (node (ref "C34") (pin "1") (pinfunction "1_1") (pintype "passive"))
      (node (ref "J1") (pin "40") (pinfunction "40_40") (pintype "passive"))
      (node (ref "R35") (pin "2") (pinfunction "2_2") (pintype "passive"))
    )
    (net (code "102") (name "Net-(C35-Pad1)") (class "Default")
      (node (ref "C35") (pin "1") (pinfunction "1_1") (pintype "passive"))
      (node (ref "J1") (pin "42") (pinfunction "42_42") (pintype "passive"))
      (node (ref "R37") (pin "2") (pinfunction "2_2") (pintype "passive"))
    )
    (net (code "103") (name "Net-(C36-Pad1)") (class "Default")
      (node (ref "C36") (pin "1") (pinfunction "1_1") (pintype "passive"))
      (node (ref "J1") (pin "44") (pinfunction "44_44") (pintype "passive"))
      (node (ref "R39") (pin "2") (pinfunction "2_2") (pintype "passive"))
    )
    (net (code "104") (name "Net-(C37-Pad1)") (class "Default")
      (node (ref "C37") (pin "1") (pinfunction "1_1") (pintype "passive"))
      (node (ref "J1") (pin "46") (pinfunction "46_46") (pintype "passive"))
      (node (ref "R41") (pin "2") (pinfunction "2_2") (pintype "passive"))
    )
    (net (code "105") (name "Net-(C38-Pad1)") (class "Default")
      (node (ref "C38") (pin "1") (pinfunction "1_1") (pintype "passive"))
      (node (ref "J1") (pin "48") (pinfunction "48_48") (pintype "passive"))
      (node (ref "R43") (pin "2") (pinfunction "2_2") (pintype "passive"))
    )
    (net (code "106") (name "Net-(C39-Pad1)") (class "Default")
      (node (ref "C39") (pin "1") (pinfunction "1_1") (pintype "passive"))
      (node (ref "J1") (pin "50") (pinfunction "50_50") (pintype "passive"))
      (node (ref "R45") (pin "2") (pinfunction "2_2") (pintype "passive"))
    )
    (net (code "107") (name "Net-(C40-Pad1)") (class "Default")
      (node (ref "C40") (pin "1") (pinfunction "1_1") (pintype "passive"))
      (node (ref "J1") (pin "52") (pinfunction "52_52") (pintype "passive"))
      (node (ref "R47") (pin "2") (pinfunction "2_2") (pintype "passive"))
    )
    (net (code "108") (name "Net-(C41-Pad1)") (class "Default")
      (node (ref "C41") (pin "1") (pinfunction "1_1") (pintype "passive"))
      (node (ref "J1") (pin "54") (pinfunction "54_54") (pintype "passive"))
      (node (ref "R49") (pin "2") (pinfunction "2_2") (pintype "passive"))
    )
    (net (code "109") (name "Net-(C42-Pad1)") (class "Default")
      (node (ref "C42") (pin "1") (pinfunction "1_1") (pintype "passive"))
      (node (ref "J1") (pin "56") (pinfunction "56_56") (pintype "passive"))
      (node (ref "R51") (pin "2") (pinfunction "2_2") (pintype "passive"))
    )
    (net (code "110") (name "Net-(C43-Pad1)") (class "Default")
      (node (ref "C43") (pin "1") (pinfunction "1_1") (pintype "passive"))
      (node (ref "J1") (pin "58") (pinfunction "58_58") (pintype "passive"))
      (node (ref "R53") (pin "2") (pinfunction "2_2") (pintype "passive"))
    )
    (net (code "111") (name "Net-(C44-Pad1)") (class "Default")
      (node (ref "C44") (pin "1") (pinfunction "1_1") (pintype "passive"))
      (node (ref "J1") (pin "60") (pinfunction "60_60") (pintype "passive"))
      (node (ref "R55") (pin "2") (pinfunction "2_2") (pintype "passive"))
    )
    (net (code "112") (name "Net-(C45-Pad1)") (class "Default")
      (node (ref "C45") (pin "1") (pinfunction "1_1") (pintype "passive"))
      (node (ref "J1") (pin "62") (pinfunction "62_62") (pintype "passive"))
      (node (ref "R57") (pin "2") (pinfunction "2_2") (pintype "passive"))
    )
    (net (code "113") (name "Net-(C46-Pad1)") (class "Default")
      (node (ref "C46") (pin "1") (pinfunction "1_1") (pintype "passive"))
      (node (ref "J1") (pin "64") (pinfunction "64_64") (pintype "passive"))
      (node (ref "R59") (pin "2") (pinfunction "2_2") (pintype "passive"))
    )
    (net (code "114") (name "Net-(C47-Pad1)") (class "Default")
      (node (ref "C47") (pin "1") (pinfunction "1_1") (pintype "passive"))
      (node (ref "J1") (pin "66") (pinfunction "66_66") (pintype "passive"))
      (node (ref "R61") (pin "2") (pinfunction "2_2") (pintype "passive"))
    )
    (net (code "115") (name "Net-(C48-Pad1)") (class "Default")
      (node (ref "C48") (pin "1") (pinfunction "1_1") (pintype "passive"))
      (node (ref "J1") (pin "68") (pinfunction "68_68") (pintype "passive"))
      (node (ref "R63") (pin "2") (pinfunction "2_2") (pintype "passive"))
    )
    (net (code "116") (name "Net-(C49-Pad1)") (class "Default")
      (node (ref "C49") (pin "1") (pinfunction "1_1") (pintype "passive"))
      (node (ref "J2") (pin "68") (pinfunction "68_68") (pintype "passive"))
      (node (ref "R64") (pin "1") (pinfunction "1_1") (pintype "passive"))
    )
    (net (code "117") (name "Net-(C50-Pad1)") (class "Default")
      (node (ref "C50") (pin "1") (pinfunction "1_1") (pintype "passive"))
      (node (ref "J2") (pin "66") (pinfunction "66_66") (pintype "passive"))
      (node (ref "R62") (pin "1") (pinfunction "1_1") (pintype "passive"))
    )
    (net (code "118") (name "Net-(C51-Pad1)") (class "Default")
      (node (ref "C51") (pin "1") (pinfunction "1_1") (pintype "passive"))
      (node (ref "J2") (pin "64") (pinfunction "64_64") (pintype "passive"))
      (node (ref "R60") (pin "1") (pinfunction "1_1") (pintype "passive"))
    )
    (net (code "119") (name "Net-(C52-Pad1)") (class "Default")
      (node (ref "C52") (pin "1") (pinfunction "1_1") (pintype "passive"))
      (node (ref "J2") (pin "62") (pinfunction "62_62") (pintype "passive"))
      (node (ref "R58") (pin "1") (pinfunction "1_1") (pintype "passive"))
    )
    (net (code "120") (name "Net-(C53-Pad1)") (class "Default")
      (node (ref "C53") (pin "1") (pinfunction "1_1") (pintype "passive"))
      (node (ref "J2") (pin "60") (pinfunction "60_60") (pintype "passive"))
      (node (ref "R56") (pin "1") (pinfunction "1_1") (pintype "passive"))
    )
    (net (code "121") (name "Net-(C54-Pad1)") (class "Default")
      (node (ref "C54") (pin "1") (pinfunction "1_1") (pintype "passive"))
      (node (ref "J2") (pin "58") (pinfunction "58_58") (pintype "passive"))
      (node (ref "R54") (pin "1") (pinfunction "1_1") (pintype "passive"))
    )
    (net (code "122") (name "Net-(C55-Pad1)") (class "Default")
      (node (ref "C55") (pin "1") (pinfunction "1_1") (pintype "passive"))
      (node (ref "J2") (pin "56") (pinfunction "56_56") (pintype "passive"))
      (node (ref "R52") (pin "1") (pinfunction "1_1") (pintype "passive"))
    )
    (net (code "123") (name "Net-(C56-Pad1)") (class "Default")
      (node (ref "C56") (pin "1") (pinfunction "1_1") (pintype "passive"))
      (node (ref "J2") (pin "54") (pinfunction "54_54") (pintype "passive"))
      (node (ref "R50") (pin "1") (pinfunction "1_1") (pintype "passive"))
    )
    (net (code "124") (name "Net-(C57-Pad1)") (class "Default")
      (node (ref "C57") (pin "1") (pinfunction "1_1") (pintype "passive"))
      (node (ref "J2") (pin "52") (pinfunction "52_52") (pintype "passive"))
      (node (ref "R48") (pin "1") (pinfunction "1_1") (pintype "passive"))
    )
    (net (code "125") (name "Net-(C58-Pad1)") (class "Default")
      (node (ref "C58") (pin "1") (pinfunction "1_1") (pintype "passive"))
      (node (ref "J2") (pin "50") (pinfunction "50_50") (pintype "passive"))
      (node (ref "R46") (pin "1") (pinfunction "1_1") (pintype "passive"))
    )
    (net (code "126") (name "Net-(C59-Pad1)") (class "Default")
      (node (ref "C59") (pin "1") (pinfunction "1_1") (pintype "passive"))
      (node (ref "J2") (pin "48") (pinfunction "48_48") (pintype "passive"))
      (node (ref "R44") (pin "1") (pinfunction "1_1") (pintype "passive"))
    )
    (net (code "127") (name "Net-(C60-Pad1)") (class "Default")
      (node (ref "C60") (pin "1") (pinfunction "1_1") (pintype "passive"))
      (node (ref "J2") (pin "46") (pinfunction "46_46") (pintype "passive"))
      (node (ref "R42") (pin "1") (pinfunction "1_1") (pintype "passive"))
    )
    (net (code "128") (name "Net-(C61-Pad1)") (class "Default")
      (node (ref "C61") (pin "1") (pinfunction "1_1") (pintype "passive"))
      (node (ref "J2") (pin "44") (pinfunction "44_44") (pintype "passive"))
      (node (ref "R40") (pin "1") (pinfunction "1_1") (pintype "passive"))
    )
    (net (code "129") (name "Net-(C62-Pad1)") (class "Default")
      (node (ref "C62") (pin "1") (pinfunction "1_1") (pintype "passive"))
      (node (ref "J2") (pin "42") (pinfunction "42_42") (pintype "passive"))
      (node (ref "R38") (pin "1") (pinfunction "1_1") (pintype "passive"))
    )
    (net (code "130") (name "Net-(C63-Pad1)") (class "Default")
      (node (ref "C63") (pin "1") (pinfunction "1_1") (pintype "passive"))
      (node (ref "J2") (pin "40") (pinfunction "40_40") (pintype "passive"))
      (node (ref "R36") (pin "1") (pinfunction "1_1") (pintype "passive"))
    )
    (net (code "131") (name "Net-(C64-Pad1)") (class "Default")
      (node (ref "C64") (pin "1") (pinfunction "1_1") (pintype "passive"))
      (node (ref "J2") (pin "38") (pinfunction "38_38") (pintype "passive"))
      (node (ref "R34") (pin "1") (pinfunction "1_1") (pintype "passive"))
    )
    (net (code "132") (name "unconnected-(J1-Pad2)") (class "Default")
      (node (ref "J1") (pin "2") (pinfunction "2_2") (pintype "passive+no_connect"))
    )
    (net (code "133") (name "unconnected-(J1-Pad4)") (class "Default")
      (node (ref "J1") (pin "4") (pinfunction "4_4") (pintype "passive+no_connect"))
    )
    (net (code "134") (name "unconnected-(J1-Pad70)") (class "Default")
      (node (ref "J1") (pin "70") (pinfunction "70_70") (pintype "passive+no_connect"))
    )
    (net (code "135") (name "unconnected-(J1-Pad72)") (class "Default")
      (node (ref "J1") (pin "72") (pinfunction "72_72") (pintype "passive+no_connect"))
    )
    (net (code "136") (name "unconnected-(J2-Pad2)") (class "Default")
      (node (ref "J2") (pin "2") (pinfunction "2_2") (pintype "passive+no_connect"))
    )
    (net (code "137") (name "unconnected-(J2-Pad4)") (class "Default")
      (node (ref "J2") (pin "4") (pinfunction "4_4") (pintype "passive+no_connect"))
    )
    (net (code "138") (name "unconnected-(J2-Pad70)") (class "Default")
      (node (ref "J2") (pin "70") (pinfunction "70_70") (pintype "passive+no_connect"))
    )
    (net (code "139") (name "unconnected-(J2-Pad72)") (class "Default")
      (node (ref "J2") (pin "72") (pinfunction "72_72") (pintype "passive+no_connect"))
    )
    (net (code "140") (name "unconnected-(J3-Pad5)") (class "Default")
      (node (ref "J3") (pin "5") (pinfunction "5_5") (pintype "passive"))
    )
    (net (code "141") (name "unconnected-(J3-Pad6)") (class "Default")
      (node (ref "J3") (pin "6") (pinfunction "6_6") (pintype "passive"))
    )
    (net (code "142") (name "unconnected-(J3-Pad15)") (class "Default")
      (node (ref "J3") (pin "15") (pinfunction "15_15") (pintype "passive"))
    )
    (net (code "143") (name "unconnected-(J3-Pad16)") (class "Default")
      (node (ref "J3") (pin "16") (pinfunction "16_16") (pintype "passive"))
    )
    (net (code "144") (name "unconnected-(J3-Pad25)") (class "Default")
      (node (ref "J3") (pin "25") (pinfunction "25_25") (pintype "passive"))
    )
    (net (code "145") (name "unconnected-(J3-Pad26)") (class "Default")
      (node (ref "J3") (pin "26") (pinfunction "26_26") (pintype "passive"))
    )
    (net (code "146") (name "unconnected-(J3-Pad35)") (class "Default")
      (node (ref "J3") (pin "35") (pinfunction "35_35") (pintype "passive"))
    )
    (net (code "147") (name "unconnected-(J3-Pad36)") (class "Default")
      (node (ref "J3") (pin "36") (pinfunction "36_36") (pintype "passive"))
    )
    (net (code "148") (name "unconnected-(J3-Pad45)") (class "Default")
      (node (ref "J3") (pin "45") (pinfunction "45_45") (pintype "passive"))
    )
    (net (code "149") (name "unconnected-(J3-Pad46)") (class "Default")
      (node (ref "J3") (pin "46") (pinfunction "46_46") (pintype "passive"))
    )
    (net (code "150") (name "unconnected-(J3-Pad55)") (class "Default")
      (node (ref "J3") (pin "55") (pinfunction "55_55") (pintype "passive"))
    )
    (net (code "151") (name "unconnected-(J3-Pad56)") (class "Default")
      (node (ref "J3") (pin "56") (pinfunction "56_56") (pintype "passive"))
    )
    (net (code "152") (name "unconnected-(J3-Pad65)") (class "Default")
      (node (ref "J3") (pin "65") (pinfunction "65_65") (pintype "passive"))
    )
    (net (code "153") (name "unconnected-(J3-Pad66)") (class "Default")
      (node (ref "J3") (pin "66") (pinfunction "66_66") (pintype "passive"))
    )
    (net (code "154") (name "unconnected-(J3-Pad75)") (class "Default")
      (node (ref "J3") (pin "75") (pinfunction "75_75") (pintype "passive"))
    )
    (net (code "155") (name "unconnected-(J3-Pad76)") (class "Default")
      (node (ref "J3") (pin "76") (pinfunction "76_76") (pintype "passive"))
    )
    (net (code "156") (name "unconnected-(J4-Pad5)") (class "Default")
      (node (ref "J4") (pin "5") (pinfunction "5_5") (pintype "passive"))
    )
    (net (code "157") (name "unconnected-(J4-Pad6)") (class "Default")
      (node (ref "J4") (pin "6") (pinfunction "6_6") (pintype "passive"))
    )
    (net (code "158") (name "unconnected-(J4-Pad15)") (class "Default")
      (node (ref "J4") (pin "15") (pinfunction "15_15") (pintype "passive"))
    )
    (net (code "159") (name "unconnected-(J4-Pad16)") (class "Default")
      (node (ref "J4") (pin "16") (pinfunction "16_16") (pintype "passive"))
    )
    (net (code "160") (name "unconnected-(J4-Pad25)") (class "Default")
      (node (ref "J4") (pin "25") (pinfunction "25_25") (pintype "passive"))
    )
    (net (code "161") (name "unconnected-(J4-Pad26)") (class "Default")
      (node (ref "J4") (pin "26") (pinfunction "26_26") (pintype "passive"))
    )
    (net (code "162") (name "unconnected-(J4-Pad35)") (class "Default")
      (node (ref "J4") (pin "35") (pinfunction "35_35") (pintype "passive"))
    )
    (net (code "163") (name "unconnected-(J4-Pad36)") (class "Default")
      (node (ref "J4") (pin "36") (pinfunction "36_36") (pintype "passive"))
    )
    (net (code "164") (name "unconnected-(J4-Pad45)") (class "Default")
      (node (ref "J4") (pin "45") (pinfunction "45_45") (pintype "passive"))
    )
    (net (code "165") (name "unconnected-(J4-Pad46)") (class "Default")
      (node (ref "J4") (pin "46") (pinfunction "46_46") (pintype "passive"))
    )
    (net (code "166") (name "unconnected-(J4-Pad55)") (class "Default")
      (node (ref "J4") (pin "55") (pinfunction "55_55") (pintype "passive"))
    )
    (net (code "167") (name "unconnected-(J4-Pad56)") (class "Default")
      (node (ref "J4") (pin "56") (pinfunction "56_56") (pintype "passive"))
    )
    (net (code "168") (name "unconnected-(J4-Pad65)") (class "Default")
      (node (ref "J4") (pin "65") (pinfunction "65_65") (pintype "passive"))
    )
    (net (code "169") (name "unconnected-(J4-Pad66)") (class "Default")
      (node (ref "J4") (pin "66") (pinfunction "66_66") (pintype "passive"))
    )
    (net (code "170") (name "unconnected-(J4-Pad75)") (class "Default")
      (node (ref "J4") (pin "75") (pinfunction "75_75") (pintype "passive"))
    )
    (net (code "171") (name "unconnected-(J4-Pad76)") (class "Default")
      (node (ref "J4") (pin "76") (pinfunction "76_76") (pintype "passive"))
    )
  )
)
